# ADS.net
KiCad netlist of a schematic drawn in Altium Designer
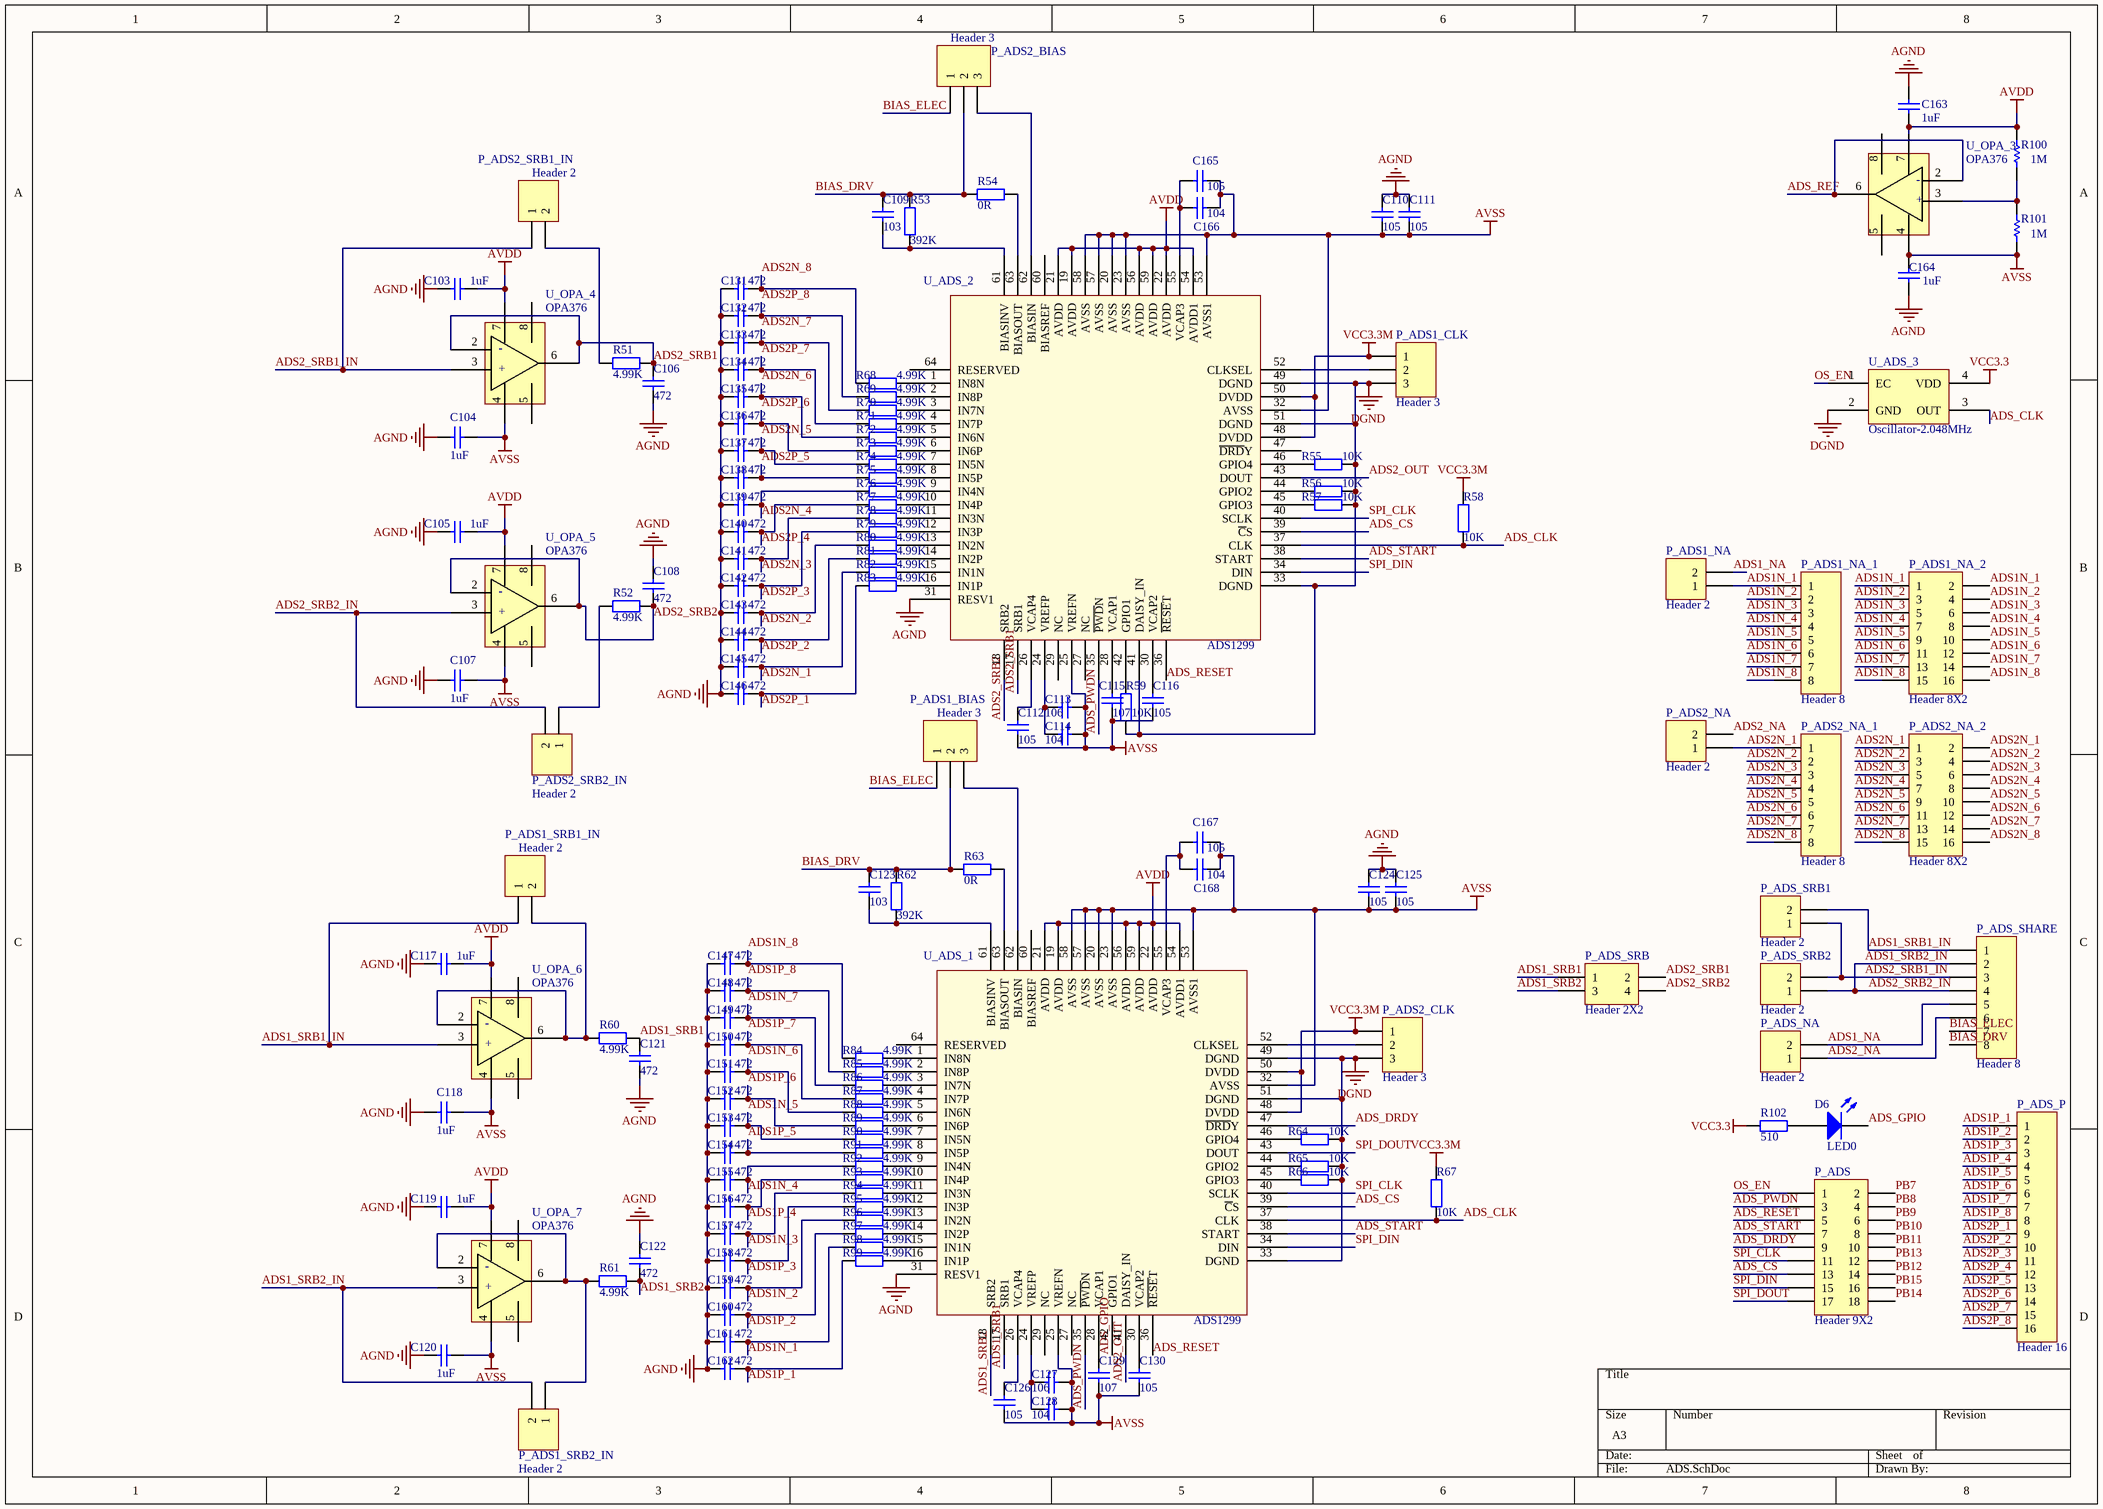
[diagram p0: ADS.SchDoc]

(export (version "E")
  (design (tool "Eeschema 10.0.6"))
  (components
    (comp (ref "C103")
      (value "1uF")
      (footprint "SMT-0603")
      (description "Capacitor")
      (fields (field (name "PUBLISHER") "Altium Limited"))
      (libsource (lib "Miscellaneous Devices") (part "Cap"))
    )
    (comp (ref "C104")
      (value "1uF")
      (footprint "SMT-0603")
      (description "Capacitor")
      (fields (field (name "PUBLISHER") "Altium Limited"))
      (libsource (lib "Miscellaneous Devices") (part "Cap"))
    )
    (comp (ref "C105")
      (value "1uF")
      (footprint "SMT-0603")
      (description "Capacitor")
      (fields (field (name "PUBLISHER") "Altium Limited"))
      (libsource (lib "Miscellaneous Devices") (part "Cap"))
    )
    (comp (ref "C106")
      (value "472")
      (footprint "SMT-0603")
      (description "Capacitor")
      (fields (field (name "Comment") "Cap") (field (name "PUBLISHER") "Altium Limited"))
      (libsource (lib "Miscellaneous Devices") (part "Cap"))
    )
    (comp (ref "C107")
      (value "1uF")
      (footprint "SMT-0603")
      (description "Capacitor")
      (fields (field (name "PUBLISHER") "Altium Limited"))
      (libsource (lib "Miscellaneous Devices") (part "Cap"))
    )
    (comp (ref "C108")
      (value "472")
      (footprint "SMT-0603")
      (description "Capacitor")
      (fields (field (name "Comment") "Cap") (field (name "PUBLISHER") "Altium Limited"))
      (libsource (lib "Miscellaneous Devices") (part "Cap"))
    )
    (comp (ref "C109")
      (value "103")
      (footprint "SMT-0603")
      (description "Capacitor")
      (fields (field (name "Comment") "Cap") (field (name "PUBLISHER") "Altium Limited"))
      (libsource (lib "Miscellaneous Devices") (part "Cap"))
    )
    (comp (ref "C110")
      (value "105")
      (footprint "SMT-0603")
      (description "Capacitor")
      (fields (field (name "Comment") "Cap") (field (name "PUBLISHER") "Altium Limited"))
      (libsource (lib "Miscellaneous Devices") (part "Cap"))
    )
    (comp (ref "C111")
      (value "105")
      (footprint "SMT-0603")
      (description "Capacitor")
      (fields (field (name "Comment") "Cap") (field (name "PUBLISHER") "Altium Limited"))
      (libsource (lib "Miscellaneous Devices") (part "Cap"))
    )
    (comp (ref "C112")
      (value "105")
      (footprint "SMT-0603")
      (description "Capacitor")
      (fields (field (name "Comment") "Cap") (field (name "PUBLISHER") "Altium Limited"))
      (libsource (lib "Miscellaneous Devices") (part "Cap"))
    )
    (comp (ref "C113")
      (value "106")
      (footprint "SMT-0603")
      (description "Capacitor")
      (fields (field (name "Comment") "Cap") (field (name "PUBLISHER") "Altium Limited"))
      (libsource (lib "Miscellaneous Devices") (part "Cap"))
    )
    (comp (ref "C114")
      (value "104")
      (footprint "SMT-0603")
      (description "Capacitor")
      (fields (field (name "Comment") "Cap") (field (name "PUBLISHER") "Altium Limited"))
      (libsource (lib "Miscellaneous Devices") (part "Cap"))
    )
    (comp (ref "C115")
      (value "107")
      (footprint "SMT-0603")
      (description "Capacitor")
      (fields (field (name "Comment") "Cap") (field (name "PUBLISHER") "Altium Limited"))
      (libsource (lib "Miscellaneous Devices") (part "Cap"))
    )
    (comp (ref "C116")
      (value "105")
      (footprint "SMT-0603")
      (description "Capacitor")
      (fields (field (name "Comment") "Cap") (field (name "PUBLISHER") "Altium Limited"))
      (libsource (lib "Miscellaneous Devices") (part "Cap"))
    )
    (comp (ref "C117")
      (value "1uF")
      (footprint "SMT-0603")
      (description "Capacitor")
      (fields (field (name "PUBLISHER") "Altium Limited"))
      (libsource (lib "Miscellaneous Devices") (part "Cap"))
    )
    (comp (ref "C118")
      (value "1uF")
      (footprint "SMT-0603")
      (description "Capacitor")
      (fields (field (name "PUBLISHER") "Altium Limited"))
      (libsource (lib "Miscellaneous Devices") (part "Cap"))
    )
    (comp (ref "C119")
      (value "1uF")
      (footprint "SMT-0603")
      (description "Capacitor")
      (fields (field (name "PUBLISHER") "Altium Limited"))
      (libsource (lib "Miscellaneous Devices") (part "Cap"))
    )
    (comp (ref "C120")
      (value "1uF")
      (footprint "SMT-0603")
      (description "Capacitor")
      (fields (field (name "PUBLISHER") "Altium Limited"))
      (libsource (lib "Miscellaneous Devices") (part "Cap"))
    )
    (comp (ref "C121")
      (value "472")
      (footprint "SMT-0603")
      (description "Capacitor")
      (fields (field (name "Comment") "Cap") (field (name "PUBLISHER") "Altium Limited"))
      (libsource (lib "Miscellaneous Devices") (part "Cap"))
    )
    (comp (ref "C122")
      (value "472")
      (footprint "SMT-0603")
      (description "Capacitor")
      (fields (field (name "Comment") "Cap") (field (name "PUBLISHER") "Altium Limited"))
      (libsource (lib "Miscellaneous Devices") (part "Cap"))
    )
    (comp (ref "C123")
      (value "103")
      (footprint "SMT-0603")
      (description "Capacitor")
      (fields (field (name "Comment") "Cap") (field (name "PUBLISHER") "Altium Limited"))
      (libsource (lib "Miscellaneous Devices") (part "Cap"))
    )
    (comp (ref "C124")
      (value "105")
      (footprint "SMT-0603")
      (description "Capacitor")
      (fields (field (name "Comment") "Cap") (field (name "PUBLISHER") "Altium Limited"))
      (libsource (lib "Miscellaneous Devices") (part "Cap"))
    )
    (comp (ref "C125")
      (value "105")
      (footprint "SMT-0603")
      (description "Capacitor")
      (fields (field (name "Comment") "Cap") (field (name "PUBLISHER") "Altium Limited"))
      (libsource (lib "Miscellaneous Devices") (part "Cap"))
    )
    (comp (ref "C126")
      (value "105")
      (footprint "SMT-0603")
      (description "Capacitor")
      (fields (field (name "Comment") "Cap") (field (name "PUBLISHER") "Altium Limited"))
      (libsource (lib "Miscellaneous Devices") (part "Cap"))
    )
    (comp (ref "C127")
      (value "106")
      (footprint "SMT-0603")
      (description "Capacitor")
      (fields (field (name "Comment") "Cap") (field (name "PUBLISHER") "Altium Limited"))
      (libsource (lib "Miscellaneous Devices") (part "Cap"))
    )
    (comp (ref "C128")
      (value "104")
      (footprint "SMT-0603")
      (description "Capacitor")
      (fields (field (name "Comment") "Cap") (field (name "PUBLISHER") "Altium Limited"))
      (libsource (lib "Miscellaneous Devices") (part "Cap"))
    )
    (comp (ref "C129")
      (value "107")
      (footprint "SMT-0603")
      (description "Capacitor")
      (fields (field (name "Comment") "Cap") (field (name "PUBLISHER") "Altium Limited"))
      (libsource (lib "Miscellaneous Devices") (part "Cap"))
    )
    (comp (ref "C130")
      (value "105")
      (footprint "SMT-0603")
      (description "Capacitor")
      (fields (field (name "Comment") "Cap") (field (name "PUBLISHER") "Altium Limited"))
      (libsource (lib "Miscellaneous Devices") (part "Cap"))
    )
    (comp (ref "C131")
      (value "472")
      (footprint "SMT-0603")
      (description "Capacitor")
      (fields (field (name "Comment") "Cap") (field (name "PUBLISHER") "Altium Limited"))
      (libsource (lib "Miscellaneous Devices") (part "Cap"))
    )
    (comp (ref "C132")
      (value "472")
      (footprint "SMT-0603")
      (description "Capacitor")
      (fields (field (name "Comment") "Cap") (field (name "PUBLISHER") "Altium Limited"))
      (libsource (lib "Miscellaneous Devices") (part "Cap"))
    )
    (comp (ref "C133")
      (value "472")
      (footprint "SMT-0603")
      (description "Capacitor")
      (fields (field (name "Comment") "Cap") (field (name "PUBLISHER") "Altium Limited"))
      (libsource (lib "Miscellaneous Devices") (part "Cap"))
    )
    (comp (ref "C134")
      (value "472")
      (footprint "SMT-0603")
      (description "Capacitor")
      (fields (field (name "Comment") "Cap") (field (name "PUBLISHER") "Altium Limited"))
      (libsource (lib "Miscellaneous Devices") (part "Cap"))
    )
    (comp (ref "C135")
      (value "472")
      (footprint "SMT-0603")
      (description "Capacitor")
      (fields (field (name "Comment") "Cap") (field (name "PUBLISHER") "Altium Limited"))
      (libsource (lib "Miscellaneous Devices") (part "Cap"))
    )
    (comp (ref "C136")
      (value "472")
      (footprint "SMT-0603")
      (description "Capacitor")
      (fields (field (name "Comment") "Cap") (field (name "PUBLISHER") "Altium Limited"))
      (libsource (lib "Miscellaneous Devices") (part "Cap"))
    )
    (comp (ref "C137")
      (value "472")
      (footprint "SMT-0603")
      (description "Capacitor")
      (fields (field (name "Comment") "Cap") (field (name "PUBLISHER") "Altium Limited"))
      (libsource (lib "Miscellaneous Devices") (part "Cap"))
    )
    (comp (ref "C138")
      (value "472")
      (footprint "SMT-0603")
      (description "Capacitor")
      (fields (field (name "Comment") "Cap") (field (name "PUBLISHER") "Altium Limited"))
      (libsource (lib "Miscellaneous Devices") (part "Cap"))
    )
    (comp (ref "C139")
      (value "472")
      (footprint "SMT-0603")
      (description "Capacitor")
      (fields (field (name "Comment") "Cap") (field (name "PUBLISHER") "Altium Limited"))
      (libsource (lib "Miscellaneous Devices") (part "Cap"))
    )
    (comp (ref "C140")
      (value "472")
      (footprint "SMT-0603")
      (description "Capacitor")
      (fields (field (name "Comment") "Cap") (field (name "PUBLISHER") "Altium Limited"))
      (libsource (lib "Miscellaneous Devices") (part "Cap"))
    )
    (comp (ref "C141")
      (value "472")
      (footprint "SMT-0603")
      (description "Capacitor")
      (fields (field (name "Comment") "Cap") (field (name "PUBLISHER") "Altium Limited"))
      (libsource (lib "Miscellaneous Devices") (part "Cap"))
    )
    (comp (ref "C142")
      (value "472")
      (footprint "SMT-0603")
      (description "Capacitor")
      (fields (field (name "Comment") "Cap") (field (name "PUBLISHER") "Altium Limited"))
      (libsource (lib "Miscellaneous Devices") (part "Cap"))
    )
    (comp (ref "C143")
      (value "472")
      (footprint "SMT-0603")
      (description "Capacitor")
      (fields (field (name "Comment") "Cap") (field (name "PUBLISHER") "Altium Limited"))
      (libsource (lib "Miscellaneous Devices") (part "Cap"))
    )
    (comp (ref "C144")
      (value "472")
      (footprint "SMT-0603")
      (description "Capacitor")
      (fields (field (name "Comment") "Cap") (field (name "PUBLISHER") "Altium Limited"))
      (libsource (lib "Miscellaneous Devices") (part "Cap"))
    )
    (comp (ref "C145")
      (value "472")
      (footprint "SMT-0603")
      (description "Capacitor")
      (fields (field (name "Comment") "Cap") (field (name "PUBLISHER") "Altium Limited"))
      (libsource (lib "Miscellaneous Devices") (part "Cap"))
    )
    (comp (ref "C146")
      (value "472")
      (footprint "SMT-0603")
      (description "Capacitor")
      (fields (field (name "Comment") "Cap") (field (name "PUBLISHER") "Altium Limited"))
      (libsource (lib "Miscellaneous Devices") (part "Cap"))
    )
    (comp (ref "C147")
      (value "472")
      (footprint "SMT-0603")
      (description "Capacitor")
      (fields (field (name "Comment") "Cap") (field (name "PUBLISHER") "Altium Limited"))
      (libsource (lib "Miscellaneous Devices") (part "Cap"))
    )
    (comp (ref "C148")
      (value "472")
      (footprint "SMT-0603")
      (description "Capacitor")
      (fields (field (name "Comment") "Cap") (field (name "PUBLISHER") "Altium Limited"))
      (libsource (lib "Miscellaneous Devices") (part "Cap"))
    )
    (comp (ref "C149")
      (value "472")
      (footprint "SMT-0603")
      (description "Capacitor")
      (fields (field (name "Comment") "Cap") (field (name "PUBLISHER") "Altium Limited"))
      (libsource (lib "Miscellaneous Devices") (part "Cap"))
    )
    (comp (ref "C150")
      (value "472")
      (footprint "SMT-0603")
      (description "Capacitor")
      (fields (field (name "Comment") "Cap") (field (name "PUBLISHER") "Altium Limited"))
      (libsource (lib "Miscellaneous Devices") (part "Cap"))
    )
    (comp (ref "C151")
      (value "472")
      (footprint "SMT-0603")
      (description "Capacitor")
      (fields (field (name "Comment") "Cap") (field (name "PUBLISHER") "Altium Limited"))
      (libsource (lib "Miscellaneous Devices") (part "Cap"))
    )
    (comp (ref "C152")
      (value "472")
      (footprint "SMT-0603")
      (description "Capacitor")
      (fields (field (name "Comment") "Cap") (field (name "PUBLISHER") "Altium Limited"))
      (libsource (lib "Miscellaneous Devices") (part "Cap"))
    )
    (comp (ref "C153")
      (value "472")
      (footprint "SMT-0603")
      (description "Capacitor")
      (fields (field (name "Comment") "Cap") (field (name "PUBLISHER") "Altium Limited"))
      (libsource (lib "Miscellaneous Devices") (part "Cap"))
    )
    (comp (ref "C154")
      (value "472")
      (footprint "SMT-0603")
      (description "Capacitor")
      (fields (field (name "Comment") "Cap") (field (name "PUBLISHER") "Altium Limited"))
      (libsource (lib "Miscellaneous Devices") (part "Cap"))
    )
    (comp (ref "C155")
      (value "472")
      (footprint "SMT-0603")
      (description "Capacitor")
      (fields (field (name "Comment") "Cap") (field (name "PUBLISHER") "Altium Limited"))
      (libsource (lib "Miscellaneous Devices") (part "Cap"))
    )
    (comp (ref "C156")
      (value "472")
      (footprint "SMT-0603")
      (description "Capacitor")
      (fields (field (name "Comment") "Cap") (field (name "PUBLISHER") "Altium Limited"))
      (libsource (lib "Miscellaneous Devices") (part "Cap"))
    )
    (comp (ref "C157")
      (value "472")
      (footprint "SMT-0603")
      (description "Capacitor")
      (fields (field (name "Comment") "Cap") (field (name "PUBLISHER") "Altium Limited"))
      (libsource (lib "Miscellaneous Devices") (part "Cap"))
    )
    (comp (ref "C158")
      (value "472")
      (footprint "SMT-0603")
      (description "Capacitor")
      (fields (field (name "Comment") "Cap") (field (name "PUBLISHER") "Altium Limited"))
      (libsource (lib "Miscellaneous Devices") (part "Cap"))
    )
    (comp (ref "C159")
      (value "472")
      (footprint "SMT-0603")
      (description "Capacitor")
      (fields (field (name "Comment") "Cap") (field (name "PUBLISHER") "Altium Limited"))
      (libsource (lib "Miscellaneous Devices") (part "Cap"))
    )
    (comp (ref "C160")
      (value "472")
      (footprint "SMT-0603")
      (description "Capacitor")
      (fields (field (name "Comment") "Cap") (field (name "PUBLISHER") "Altium Limited"))
      (libsource (lib "Miscellaneous Devices") (part "Cap"))
    )
    (comp (ref "C161")
      (value "472")
      (footprint "SMT-0603")
      (description "Capacitor")
      (fields (field (name "Comment") "Cap") (field (name "PUBLISHER") "Altium Limited"))
      (libsource (lib "Miscellaneous Devices") (part "Cap"))
    )
    (comp (ref "C162")
      (value "472")
      (footprint "SMT-0603")
      (description "Capacitor")
      (fields (field (name "Comment") "Cap") (field (name "PUBLISHER") "Altium Limited"))
      (libsource (lib "Miscellaneous Devices") (part "Cap"))
    )
    (comp (ref "C163")
      (value "1uF")
      (footprint "SMT-0603")
      (description "Capacitor")
      (fields (field (name "PUBLISHER") "Altium Limited"))
      (libsource (lib "Miscellaneous Devices") (part "Cap"))
    )
    (comp (ref "C164")
      (value "1uF")
      (footprint "SMT-0603")
      (description "Capacitor")
      (fields (field (name "PUBLISHER") "Altium Limited"))
      (libsource (lib "Miscellaneous Devices") (part "Cap"))
    )
    (comp (ref "C165")
      (value "105")
      (footprint "SMT-0603")
      (description "Capacitor")
      (fields (field (name "Comment") "Cap") (field (name "PUBLISHER") "Altium Limited"))
      (libsource (lib "Miscellaneous Devices") (part "Cap"))
    )
    (comp (ref "C166")
      (value "104")
      (footprint "SMT-0603")
      (description "Capacitor")
      (fields (field (name "Comment") "Cap") (field (name "PUBLISHER") "Altium Limited"))
      (libsource (lib "Miscellaneous Devices") (part "Cap"))
    )
    (comp (ref "C167")
      (value "105")
      (footprint "SMT-0603")
      (description "Capacitor")
      (fields (field (name "Comment") "Cap") (field (name "PUBLISHER") "Altium Limited"))
      (libsource (lib "Miscellaneous Devices") (part "Cap"))
    )
    (comp (ref "C168")
      (value "104")
      (footprint "SMT-0603")
      (description "Capacitor")
      (fields (field (name "Comment") "Cap") (field (name "PUBLISHER") "Altium Limited"))
      (libsource (lib "Miscellaneous Devices") (part "Cap"))
    )
    (comp (ref "D6")
      (value "LED0")
      (footprint "K3528")
      (description "Typical INFRARED GaAs LED")
      (fields (field (name "PUBLISHER") "Altium Limited"))
      (libsource (lib "Miscellaneous Devices") (part "LED0"))
    )
    (comp (ref "P_ADS")
      (value "Header 9X2")
      (footprint "HDR2X9")
      (description "Header, 9-Pin, Dual row")
      (fields (field (name "PUBLISHER") "Altium Limited"))
      (libsource (lib "Miscellaneous Connectors") (part "Header 9X2"))
    )
    (comp (ref "P_ADS1_BIAS")
      (value "Header 3")
      (footprint "HDR1X3")
      (description "Header, 3-Pin")
      (fields (field (name "PUBLISHER") "Altium Limited"))
      (libsource (lib "Miscellaneous Connectors") (part "Header 3"))
    )
    (comp (ref "P_ADS1_CLK")
      (value "Header 3")
      (footprint "HDR1X3")
      (description "Header, 3-Pin")
      (fields (field (name "PUBLISHER") "Altium Limited"))
      (libsource (lib "") (part "Header 3_1"))
    )
    (comp (ref "P_ADS1_NA")
      (value "Header 2")
      (footprint "HDR1X2")
      (description "Header, 2-Pin")
      (fields (field (name "PUBLISHER") "Altium Limited"))
      (libsource (lib "Miscellaneous Connectors") (part "Header 2"))
    )
    (comp (ref "P_ADS1_NA_1")
      (value "Header 8")
      (footprint "HDR1X8")
      (description "Header, 8-Pin")
      (fields (field (name "PUBLISHER") "Altium Limited"))
      (libsource (lib "Miscellaneous Connectors") (part "Header 8"))
    )
    (comp (ref "P_ADS1_NA_2")
      (value "Header 8X2")
      (footprint "HDR2X8")
      (description "Header, 8-Pin, Dual row")
      (fields (field (name "PUBLISHER") "Altium Limited"))
      (libsource (lib "Miscellaneous Connectors") (part "Header 8X2"))
    )
    (comp (ref "P_ADS1_SRB1_IN")
      (value "Header 2")
      (footprint "HDR1X2")
      (description "Header, 2-Pin")
      (fields (field (name "PUBLISHER") "Altium Limited"))
      (libsource (lib "") (part "Header 2_1"))
    )
    (comp (ref "P_ADS1_SRB2_IN")
      (value "Header 2")
      (footprint "HDR1X2")
      (description "Header, 2-Pin")
      (fields (field (name "PUBLISHER") "Altium Limited"))
      (libsource (lib "") (part "Header 2_2"))
    )
    (comp (ref "P_ADS2_BIAS")
      (value "Header 3")
      (footprint "HDR1X3")
      (description "Header, 3-Pin")
      (fields (field (name "PUBLISHER") "Altium Limited"))
      (libsource (lib "Miscellaneous Connectors") (part "Header 3"))
    )
    (comp (ref "P_ADS2_CLK")
      (value "Header 3")
      (footprint "HDR1X3")
      (description "Header, 3-Pin")
      (fields (field (name "PUBLISHER") "Altium Limited"))
      (libsource (lib "") (part "Header 3_1"))
    )
    (comp (ref "P_ADS2_NA")
      (value "Header 2")
      (footprint "HDR1X2")
      (description "Header, 2-Pin")
      (fields (field (name "PUBLISHER") "Altium Limited"))
      (libsource (lib "Miscellaneous Connectors") (part "Header 2"))
    )
    (comp (ref "P_ADS2_NA_1")
      (value "Header 8")
      (footprint "HDR1X8")
      (description "Header, 8-Pin")
      (fields (field (name "PUBLISHER") "Altium Limited"))
      (libsource (lib "Miscellaneous Connectors") (part "Header 8"))
    )
    (comp (ref "P_ADS2_NA_2")
      (value "Header 8X2")
      (footprint "HDR2X8")
      (description "Header, 8-Pin, Dual row")
      (fields (field (name "PUBLISHER") "Altium Limited"))
      (libsource (lib "Miscellaneous Connectors") (part "Header 8X2"))
    )
    (comp (ref "P_ADS2_SRB1_IN")
      (value "Header 2")
      (footprint "HDR1X2")
      (description "Header, 2-Pin")
      (fields (field (name "PUBLISHER") "Altium Limited"))
      (libsource (lib "") (part "Header 2_1"))
    )
    (comp (ref "P_ADS2_SRB2_IN")
      (value "Header 2")
      (footprint "HDR1X2")
      (description "Header, 2-Pin")
      (fields (field (name "PUBLISHER") "Altium Limited"))
      (libsource (lib "") (part "Header 2_2"))
    )
    (comp (ref "P_ADS_NA")
      (value "Header 2")
      (footprint "HDR1X2")
      (description "Header, 2-Pin")
      (fields (field (name "PUBLISHER") "Altium Limited"))
      (libsource (lib "Miscellaneous Connectors") (part "Header 2"))
    )
    (comp (ref "P_ADS_P")
      (value "Header 16")
      (footprint "HDR1X16")
      (description "Header, 16-Pin")
      (fields (field (name "PUBLISHER") "Altium Limited"))
      (libsource (lib "Miscellaneous Connectors") (part "Header 16"))
    )
    (comp (ref "P_ADS_SHARE")
      (value "Header 8")
      (footprint "HDR1X8")
      (description "Header, 8-Pin")
      (fields (field (name "PUBLISHER") "Altium Limited"))
      (libsource (lib "Miscellaneous Connectors") (part "Header 8"))
    )
    (comp (ref "P_ADS_SRB")
      (value "Header 2X2")
      (footprint "HDR2X2")
      (description "Header, 2-Pin, Dual row")
      (fields (field (name "PUBLISHER") "Altium Limited"))
      (libsource (lib "Miscellaneous Connectors") (part "Header 2X2"))
    )
    (comp (ref "P_ADS_SRB1")
      (value "Header 2")
      (footprint "HDR1X2")
      (description "Header, 2-Pin")
      (fields (field (name "PUBLISHER") "Altium Limited"))
      (libsource (lib "Miscellaneous Connectors") (part "Header 2"))
    )
    (comp (ref "P_ADS_SRB2")
      (value "Header 2")
      (footprint "HDR1X2")
      (description "Header, 2-Pin")
      (fields (field (name "PUBLISHER") "Altium Limited"))
      (libsource (lib "Miscellaneous Connectors") (part "Header 2"))
    )
    (comp (ref "R51")
      (value "4.99K")
      (footprint "SMT-0603")
      (description "Resistor")
      (fields (field (name "Comment") "Res2") (field (name "PUBLISHER") "Altium Limited"))
      (libsource (lib "Miscellaneous Devices") (part "Res2"))
    )
    (comp (ref "R52")
      (value "4.99K")
      (footprint "SMT-0603")
      (description "Resistor")
      (fields (field (name "Comment") "Res2") (field (name "PUBLISHER") "Altium Limited"))
      (libsource (lib "Miscellaneous Devices") (part "Res2"))
    )
    (comp (ref "R53")
      (value "392K")
      (footprint "SMT-0603")
      (description "Resistor")
      (fields (field (name "Comment") "Res2") (field (name "PUBLISHER") "Altium Limited"))
      (libsource (lib "") (part "Res2_1"))
    )
    (comp (ref "R54")
      (value "0R")
      (footprint "SMT-0603")
      (description "Resistor")
      (fields (field (name "Comment") "Res2") (field (name "PUBLISHER") "Altium Limited"))
      (libsource (lib "Miscellaneous Devices") (part "Res2"))
    )
    (comp (ref "R55")
      (value "10K")
      (footprint "SMT-0603")
      (description "Resistor")
      (fields (field (name "Comment") "Res2") (field (name "PUBLISHER") "Altium Limited"))
      (libsource (lib "Miscellaneous Devices") (part "Res2"))
    )
    (comp (ref "R56")
      (value "10K")
      (footprint "SMT-0603")
      (description "Resistor")
      (fields (field (name "Comment") "Res2") (field (name "PUBLISHER") "Altium Limited"))
      (libsource (lib "Miscellaneous Devices") (part "Res2"))
    )
    (comp (ref "R57")
      (value "10K")
      (footprint "SMT-0603")
      (description "Resistor")
      (fields (field (name "Comment") "Res2") (field (name "PUBLISHER") "Altium Limited"))
      (libsource (lib "Miscellaneous Devices") (part "Res2"))
    )
    (comp (ref "R58")
      (value "10K")
      (footprint "SMT-0603")
      (description "Resistor")
      (fields (field (name "Comment") "Res2") (field (name "PUBLISHER") "Altium Limited"))
      (libsource (lib "") (part "Res2_1"))
    )
    (comp (ref "R59")
      (value "10K")
      (footprint "SMT-0603")
      (description "Resistor")
      (fields (field (name "Comment") "Res2") (field (name "PUBLISHER") "Altium Limited"))
      (libsource (lib "") (part "Res2_1"))
    )
    (comp (ref "R60")
      (value "4.99K")
      (footprint "SMT-0603")
      (description "Resistor")
      (fields (field (name "Comment") "Res2") (field (name "PUBLISHER") "Altium Limited"))
      (libsource (lib "Miscellaneous Devices") (part "Res2"))
    )
    (comp (ref "R61")
      (value "4.99K")
      (footprint "SMT-0603")
      (description "Resistor")
      (fields (field (name "Comment") "Res2") (field (name "PUBLISHER") "Altium Limited"))
      (libsource (lib "Miscellaneous Devices") (part "Res2"))
    )
    (comp (ref "R62")
      (value "392K")
      (footprint "SMT-0603")
      (description "Resistor")
      (fields (field (name "Comment") "Res2") (field (name "PUBLISHER") "Altium Limited"))
      (libsource (lib "") (part "Res2_1"))
    )
    (comp (ref "R63")
      (value "0R")
      (footprint "SMT-0603")
      (description "Resistor")
      (fields (field (name "Comment") "Res2") (field (name "PUBLISHER") "Altium Limited"))
      (libsource (lib "Miscellaneous Devices") (part "Res2"))
    )
    (comp (ref "R64")
      (value "10K")
      (footprint "SMT-0603")
      (description "Resistor")
      (fields (field (name "Comment") "Res2") (field (name "PUBLISHER") "Altium Limited"))
      (libsource (lib "Miscellaneous Devices") (part "Res2"))
    )
    (comp (ref "R65")
      (value "10K")
      (footprint "SMT-0603")
      (description "Resistor")
      (fields (field (name "Comment") "Res2") (field (name "PUBLISHER") "Altium Limited"))
      (libsource (lib "Miscellaneous Devices") (part "Res2"))
    )
    (comp (ref "R66")
      (value "10K")
      (footprint "SMT-0603")
      (description "Resistor")
      (fields (field (name "Comment") "Res2") (field (name "PUBLISHER") "Altium Limited"))
      (libsource (lib "Miscellaneous Devices") (part "Res2"))
    )
    (comp (ref "R67")
      (value "10K")
      (footprint "SMT-0603")
      (description "Resistor")
      (fields (field (name "Comment") "Res2") (field (name "PUBLISHER") "Altium Limited"))
      (libsource (lib "") (part "Res2_1"))
    )
    (comp (ref "R68")
      (value "4.99K")
      (footprint "SMT-0603")
      (description "Resistor")
      (fields (field (name "Comment") "Res2") (field (name "PUBLISHER") "Altium Limited"))
      (libsource (lib "Miscellaneous Devices") (part "Res2"))
    )
    (comp (ref "R69")
      (value "4.99K")
      (footprint "SMT-0603")
      (description "Resistor")
      (fields (field (name "Comment") "Res2") (field (name "PUBLISHER") "Altium Limited"))
      (libsource (lib "Miscellaneous Devices") (part "Res2"))
    )
    (comp (ref "R70")
      (value "4.99K")
      (footprint "SMT-0603")
      (description "Resistor")
      (fields (field (name "Comment") "Res2") (field (name "PUBLISHER") "Altium Limited"))
      (libsource (lib "Miscellaneous Devices") (part "Res2"))
    )
    (comp (ref "R71")
      (value "4.99K")
      (footprint "SMT-0603")
      (description "Resistor")
      (fields (field (name "Comment") "Res2") (field (name "PUBLISHER") "Altium Limited"))
      (libsource (lib "Miscellaneous Devices") (part "Res2"))
    )
    (comp (ref "R72")
      (value "4.99K")
      (footprint "SMT-0603")
      (description "Resistor")
      (fields (field (name "Comment") "Res2") (field (name "PUBLISHER") "Altium Limited"))
      (libsource (lib "Miscellaneous Devices") (part "Res2"))
    )
    (comp (ref "R73")
      (value "4.99K")
      (footprint "SMT-0603")
      (description "Resistor")
      (fields (field (name "Comment") "Res2") (field (name "PUBLISHER") "Altium Limited"))
      (libsource (lib "Miscellaneous Devices") (part "Res2"))
    )
    (comp (ref "R74")
      (value "4.99K")
      (footprint "SMT-0603")
      (description "Resistor")
      (fields (field (name "Comment") "Res2") (field (name "PUBLISHER") "Altium Limited"))
      (libsource (lib "Miscellaneous Devices") (part "Res2"))
    )
    (comp (ref "R75")
      (value "4.99K")
      (footprint "SMT-0603")
      (description "Resistor")
      (fields (field (name "Comment") "Res2") (field (name "PUBLISHER") "Altium Limited"))
      (libsource (lib "Miscellaneous Devices") (part "Res2"))
    )
    (comp (ref "R76")
      (value "4.99K")
      (footprint "SMT-0603")
      (description "Resistor")
      (fields (field (name "Comment") "Res2") (field (name "PUBLISHER") "Altium Limited"))
      (libsource (lib "Miscellaneous Devices") (part "Res2"))
    )
    (comp (ref "R77")
      (value "4.99K")
      (footprint "SMT-0603")
      (description "Resistor")
      (fields (field (name "Comment") "Res2") (field (name "PUBLISHER") "Altium Limited"))
      (libsource (lib "Miscellaneous Devices") (part "Res2"))
    )
    (comp (ref "R78")
      (value "4.99K")
      (footprint "SMT-0603")
      (description "Resistor")
      (fields (field (name "Comment") "Res2") (field (name "PUBLISHER") "Altium Limited"))
      (libsource (lib "Miscellaneous Devices") (part "Res2"))
    )
    (comp (ref "R79")
      (value "4.99K")
      (footprint "SMT-0603")
      (description "Resistor")
      (fields (field (name "Comment") "Res2") (field (name "PUBLISHER") "Altium Limited"))
      (libsource (lib "Miscellaneous Devices") (part "Res2"))
    )
    (comp (ref "R80")
      (value "4.99K")
      (footprint "SMT-0603")
      (description "Resistor")
      (fields (field (name "Comment") "Res2") (field (name "PUBLISHER") "Altium Limited"))
      (libsource (lib "Miscellaneous Devices") (part "Res2"))
    )
    (comp (ref "R81")
      (value "4.99K")
      (footprint "SMT-0603")
      (description "Resistor")
      (fields (field (name "Comment") "Res2") (field (name "PUBLISHER") "Altium Limited"))
      (libsource (lib "Miscellaneous Devices") (part "Res2"))
    )
    (comp (ref "R82")
      (value "4.99K")
      (footprint "SMT-0603")
      (description "Resistor")
      (fields (field (name "Comment") "Res2") (field (name "PUBLISHER") "Altium Limited"))
      (libsource (lib "Miscellaneous Devices") (part "Res2"))
    )
    (comp (ref "R83")
      (value "4.99K")
      (footprint "SMT-0603")
      (description "Resistor")
      (fields (field (name "Comment") "Res2") (field (name "PUBLISHER") "Altium Limited"))
      (libsource (lib "Miscellaneous Devices") (part "Res2"))
    )
    (comp (ref "R84")
      (value "4.99K")
      (footprint "SMT-0603")
      (description "Resistor")
      (fields (field (name "Comment") "Res2") (field (name "PUBLISHER") "Altium Limited"))
      (libsource (lib "Miscellaneous Devices") (part "Res2"))
    )
    (comp (ref "R85")
      (value "4.99K")
      (footprint "SMT-0603")
      (description "Resistor")
      (fields (field (name "Comment") "Res2") (field (name "PUBLISHER") "Altium Limited"))
      (libsource (lib "Miscellaneous Devices") (part "Res2"))
    )
    (comp (ref "R86")
      (value "4.99K")
      (footprint "SMT-0603")
      (description "Resistor")
      (fields (field (name "Comment") "Res2") (field (name "PUBLISHER") "Altium Limited"))
      (libsource (lib "Miscellaneous Devices") (part "Res2"))
    )
    (comp (ref "R87")
      (value "4.99K")
      (footprint "SMT-0603")
      (description "Resistor")
      (fields (field (name "Comment") "Res2") (field (name "PUBLISHER") "Altium Limited"))
      (libsource (lib "Miscellaneous Devices") (part "Res2"))
    )
    (comp (ref "R88")
      (value "4.99K")
      (footprint "SMT-0603")
      (description "Resistor")
      (fields (field (name "Comment") "Res2") (field (name "PUBLISHER") "Altium Limited"))
      (libsource (lib "Miscellaneous Devices") (part "Res2"))
    )
    (comp (ref "R89")
      (value "4.99K")
      (footprint "SMT-0603")
      (description "Resistor")
      (fields (field (name "Comment") "Res2") (field (name "PUBLISHER") "Altium Limited"))
      (libsource (lib "Miscellaneous Devices") (part "Res2"))
    )
    (comp (ref "R90")
      (value "4.99K")
      (footprint "SMT-0603")
      (description "Resistor")
      (fields (field (name "Comment") "Res2") (field (name "PUBLISHER") "Altium Limited"))
      (libsource (lib "Miscellaneous Devices") (part "Res2"))
    )
    (comp (ref "R91")
      (value "4.99K")
      (footprint "SMT-0603")
      (description "Resistor")
      (fields (field (name "Comment") "Res2") (field (name "PUBLISHER") "Altium Limited"))
      (libsource (lib "Miscellaneous Devices") (part "Res2"))
    )
    (comp (ref "R92")
      (value "4.99K")
      (footprint "SMT-0603")
      (description "Resistor")
      (fields (field (name "Comment") "Res2") (field (name "PUBLISHER") "Altium Limited"))
      (libsource (lib "Miscellaneous Devices") (part "Res2"))
    )
    (comp (ref "R93")
      (value "4.99K")
      (footprint "SMT-0603")
      (description "Resistor")
      (fields (field (name "Comment") "Res2") (field (name "PUBLISHER") "Altium Limited"))
      (libsource (lib "Miscellaneous Devices") (part "Res2"))
    )
    (comp (ref "R94")
      (value "4.99K")
      (footprint "SMT-0603")
      (description "Resistor")
      (fields (field (name "Comment") "Res2") (field (name "PUBLISHER") "Altium Limited"))
      (libsource (lib "Miscellaneous Devices") (part "Res2"))
    )
    (comp (ref "R95")
      (value "4.99K")
      (footprint "SMT-0603")
      (description "Resistor")
      (fields (field (name "Comment") "Res2") (field (name "PUBLISHER") "Altium Limited"))
      (libsource (lib "Miscellaneous Devices") (part "Res2"))
    )
    (comp (ref "R96")
      (value "4.99K")
      (footprint "SMT-0603")
      (description "Resistor")
      (fields (field (name "Comment") "Res2") (field (name "PUBLISHER") "Altium Limited"))
      (libsource (lib "Miscellaneous Devices") (part "Res2"))
    )
    (comp (ref "R97")
      (value "4.99K")
      (footprint "SMT-0603")
      (description "Resistor")
      (fields (field (name "Comment") "Res2") (field (name "PUBLISHER") "Altium Limited"))
      (libsource (lib "Miscellaneous Devices") (part "Res2"))
    )
    (comp (ref "R98")
      (value "4.99K")
      (footprint "SMT-0603")
      (description "Resistor")
      (fields (field (name "Comment") "Res2") (field (name "PUBLISHER") "Altium Limited"))
      (libsource (lib "Miscellaneous Devices") (part "Res2"))
    )
    (comp (ref "R99")
      (value "4.99K")
      (footprint "SMT-0603")
      (description "Resistor")
      (fields (field (name "Comment") "Res2") (field (name "PUBLISHER") "Altium Limited"))
      (libsource (lib "Miscellaneous Devices") (part "Res2"))
    )
    (comp (ref "R100")
      (value "1M")
      (footprint "SMT-0603")
      (description "Resistor")
      (fields (field (name "PUBLISHER") "Altium Limited"))
      (libsource (lib "Miscellaneous Devices") (part "Res1"))
    )
    (comp (ref "R101")
      (value "1M")
      (footprint "SMT-0603")
      (description "Resistor")
      (fields (field (name "PUBLISHER") "Altium Limited"))
      (libsource (lib "Miscellaneous Devices") (part "Res1"))
    )
    (comp (ref "R102")
      (value "510")
      (footprint "SMT-0603")
      (description "Resistor")
      (fields (field (name "Comment") "Res2") (field (name "PUBLISHER") "Altium Limited"))
      (libsource (lib "Miscellaneous Devices") (part "Res2"))
    )
    (comp (ref "U_ADS_1") (value "ADS1299") (footprint "LQFP64") (libsource (lib "*") (part "ADS1299")))
    (comp (ref "U_ADS_2") (value "ADS1299") (footprint "LQFP64") (libsource (lib "*") (part "ADS1299")))
    (comp (ref "U_ADS_3")
      (value "Oscillator-2.048MHz")
      (footprint "3225")
      (libsource (lib "STM_ALL") (part "Oscillator-2.048MHz"))
    )
    (comp (ref "U_OPA_3") (value "OPA376") (footprint "SOP8") (libsource (lib "") (part "OPA376_1")))
    (comp (ref "U_OPA_4") (value "OPA376") (footprint "SOP8") (libsource (lib "*") (part "OPA376")))
    (comp (ref "U_OPA_5") (value "OPA376") (footprint "SOP8") (libsource (lib "*") (part "OPA376")))
    (comp (ref "U_OPA_6") (value "OPA376") (footprint "SOP8") (libsource (lib "*") (part "OPA376")))
    (comp (ref "U_OPA_7") (value "OPA376") (footprint "SOP8") (libsource (lib "*") (part "OPA376")))
  )
  (nets
    (net (code "1") (name "/ADS1N_1") (class "Default")
      (node (ref "C161") (pin "2") (pinfunction "2_2") (pintype "passive"))
      (node (ref "P_ADS1_NA") (pin "1") (pinfunction "1_1") (pintype "passive"))
      (node (ref "P_ADS1_NA_1") (pin "1") (pinfunction "1_1") (pintype "passive"))
      (node (ref "P_ADS1_NA_2") (pin "1") (pinfunction "1_1") (pintype "passive"))
      (node (ref "P_ADS1_NA_2") (pin "2") (pinfunction "2_2") (pintype "passive"))
      (node (ref "R98") (pin "1") (pinfunction "1_1") (pintype "passive"))
    )
    (net (code "2") (name "/ADS1N_2") (class "Default")
      (node (ref "C159") (pin "2") (pinfunction "2_2") (pintype "passive"))
      (node (ref "P_ADS1_NA_1") (pin "2") (pinfunction "2_2") (pintype "passive"))
      (node (ref "P_ADS1_NA_2") (pin "3") (pinfunction "3_3") (pintype "passive"))
      (node (ref "P_ADS1_NA_2") (pin "4") (pinfunction "4_4") (pintype "passive"))
      (node (ref "R96") (pin "1") (pinfunction "1_1") (pintype "passive"))
    )
    (net (code "3") (name "/ADS1N_3") (class "Default")
      (node (ref "C157") (pin "2") (pinfunction "2_2") (pintype "passive"))
      (node (ref "P_ADS1_NA_1") (pin "3") (pinfunction "3_3") (pintype "passive"))
      (node (ref "P_ADS1_NA_2") (pin "5") (pinfunction "5_5") (pintype "passive"))
      (node (ref "P_ADS1_NA_2") (pin "6") (pinfunction "6_6") (pintype "passive"))
      (node (ref "R94") (pin "1") (pinfunction "1_1") (pintype "passive"))
    )
    (net (code "4") (name "/ADS1N_4") (class "Default")
      (node (ref "C155") (pin "2") (pinfunction "2_2") (pintype "passive"))
      (node (ref "P_ADS1_NA_1") (pin "4") (pinfunction "4_4") (pintype "passive"))
      (node (ref "P_ADS1_NA_2") (pin "7") (pinfunction "7_7") (pintype "passive"))
      (node (ref "P_ADS1_NA_2") (pin "8") (pinfunction "8_8") (pintype "passive"))
      (node (ref "R92") (pin "1") (pinfunction "1_1") (pintype "passive"))
    )
    (net (code "5") (name "/ADS1N_5") (class "Default")
      (node (ref "C153") (pin "2") (pinfunction "2_2") (pintype "passive"))
      (node (ref "P_ADS1_NA_1") (pin "5") (pinfunction "5_5") (pintype "passive"))
      (node (ref "P_ADS1_NA_2") (pin "10") (pinfunction "10_10") (pintype "passive"))
      (node (ref "P_ADS1_NA_2") (pin "9") (pinfunction "9_9") (pintype "passive"))
      (node (ref "R90") (pin "1") (pinfunction "1_1") (pintype "passive"))
    )
    (net (code "6") (name "/ADS1N_6") (class "Default")
      (node (ref "C151") (pin "2") (pinfunction "2_2") (pintype "passive"))
      (node (ref "P_ADS1_NA_1") (pin "6") (pinfunction "6_6") (pintype "passive"))
      (node (ref "P_ADS1_NA_2") (pin "11") (pinfunction "11_11") (pintype "passive"))
      (node (ref "P_ADS1_NA_2") (pin "12") (pinfunction "12_12") (pintype "passive"))
      (node (ref "R88") (pin "1") (pinfunction "1_1") (pintype "passive"))
    )
    (net (code "7") (name "/ADS1N_7") (class "Default")
      (node (ref "C149") (pin "2") (pinfunction "2_2") (pintype "passive"))
      (node (ref "P_ADS1_NA_1") (pin "7") (pinfunction "7_7") (pintype "passive"))
      (node (ref "P_ADS1_NA_2") (pin "13") (pinfunction "13_13") (pintype "passive"))
      (node (ref "P_ADS1_NA_2") (pin "14") (pinfunction "14_14") (pintype "passive"))
      (node (ref "R86") (pin "1") (pinfunction "1_1") (pintype "passive"))
    )
    (net (code "8") (name "/ADS1N_8") (class "Default")
      (node (ref "C147") (pin "2") (pinfunction "2_2") (pintype "passive"))
      (node (ref "P_ADS1_NA_1") (pin "8") (pinfunction "8_8") (pintype "passive"))
      (node (ref "P_ADS1_NA_2") (pin "15") (pinfunction "15_15") (pintype "passive"))
      (node (ref "P_ADS1_NA_2") (pin "16") (pinfunction "16_16") (pintype "passive"))
      (node (ref "R84") (pin "1") (pinfunction "1_1") (pintype "passive"))
    )
    (net (code "9") (name "/ADS1P_1") (class "Default")
      (node (ref "C162") (pin "2") (pinfunction "2_2") (pintype "passive"))
      (node (ref "P_ADS_P") (pin "1") (pinfunction "1_1") (pintype "passive"))
      (node (ref "R99") (pin "1") (pinfunction "1_1") (pintype "passive"))
    )
    (net (code "10") (name "/ADS1P_2") (class "Default")
      (node (ref "C160") (pin "2") (pinfunction "2_2") (pintype "passive"))
      (node (ref "P_ADS_P") (pin "2") (pinfunction "2_2") (pintype "passive"))
      (node (ref "R97") (pin "1") (pinfunction "1_1") (pintype "passive"))
    )
    (net (code "11") (name "/ADS1P_3") (class "Default")
      (node (ref "C158") (pin "2") (pinfunction "2_2") (pintype "passive"))
      (node (ref "P_ADS_P") (pin "3") (pinfunction "3_3") (pintype "passive"))
      (node (ref "R95") (pin "1") (pinfunction "1_1") (pintype "passive"))
    )
    (net (code "12") (name "/ADS1P_4") (class "Default")
      (node (ref "C156") (pin "2") (pinfunction "2_2") (pintype "passive"))
      (node (ref "P_ADS_P") (pin "4") (pinfunction "4_4") (pintype "passive"))
      (node (ref "R93") (pin "1") (pinfunction "1_1") (pintype "passive"))
    )
    (net (code "13") (name "/ADS1P_5") (class "Default")
      (node (ref "C154") (pin "2") (pinfunction "2_2") (pintype "passive"))
      (node (ref "P_ADS_P") (pin "5") (pinfunction "5_5") (pintype "passive"))
      (node (ref "R91") (pin "1") (pinfunction "1_1") (pintype "passive"))
    )
    (net (code "14") (name "/ADS1P_6") (class "Default")
      (node (ref "C152") (pin "2") (pinfunction "2_2") (pintype "passive"))
      (node (ref "P_ADS_P") (pin "6") (pinfunction "6_6") (pintype "passive"))
      (node (ref "R89") (pin "1") (pinfunction "1_1") (pintype "passive"))
    )
    (net (code "15") (name "/ADS1P_7") (class "Default")
      (node (ref "C150") (pin "2") (pinfunction "2_2") (pintype "passive"))
      (node (ref "P_ADS_P") (pin "7") (pinfunction "7_7") (pintype "passive"))
      (node (ref "R87") (pin "1") (pinfunction "1_1") (pintype "passive"))
    )
    (net (code "16") (name "/ADS1P_8") (class "Default")
      (node (ref "C148") (pin "2") (pinfunction "2_2") (pintype "passive"))
      (node (ref "P_ADS_P") (pin "8") (pinfunction "8_8") (pintype "passive"))
      (node (ref "R85") (pin "1") (pinfunction "1_1") (pintype "passive"))
    )
    (net (code "17") (name "/ADS1_NA") (class "Default")
      (node (ref "P_ADS1_NA") (pin "2") (pinfunction "2_2") (pintype "passive"))
      (node (ref "P_ADS_NA") (pin "2") (pinfunction "2_2") (pintype "passive"))
      (node (ref "P_ADS_SHARE") (pin "5") (pinfunction "5_5") (pintype "passive"))
    )
    (net (code "18") (name "/ADS1_SRB1") (class "Default")
      (node (ref "C121") (pin "2") (pinfunction "2_2") (pintype "passive"))
      (node (ref "P_ADS_SRB") (pin "1") (pinfunction "1_1") (pintype "passive"))
      (node (ref "R60") (pin "2") (pinfunction "2_2") (pintype "passive"))
      (node (ref "U_ADS_1") (pin "17") (pinfunction "SRB1_17") (pintype "passive"))
    )
    (net (code "19") (name "/ADS1_SRB1_IN") (class "Default")
      (node (ref "P_ADS1_SRB1_IN") (pin "1") (pinfunction "1_1") (pintype "passive"))
      (node (ref "P_ADS_SHARE") (pin "1") (pinfunction "1_1") (pintype "passive"))
      (node (ref "P_ADS_SRB1") (pin "2") (pinfunction "2_2") (pintype "passive"))
      (node (ref "U_OPA_6") (pin "3") (pintype "passive"))
    )
    (net (code "20") (name "/ADS1_SRB2") (class "Default")
      (node (ref "C122") (pin "1") (pinfunction "1_1") (pintype "passive"))
      (node (ref "P_ADS_SRB") (pin "3") (pinfunction "3_3") (pintype "passive"))
      (node (ref "R61") (pin "2") (pinfunction "2_2") (pintype "passive"))
      (node (ref "U_ADS_1") (pin "18") (pinfunction "SRB2_18") (pintype "passive"))
    )
    (net (code "21") (name "/ADS1_SRB2_IN") (class "Default")
      (node (ref "P_ADS1_SRB2_IN") (pin "2") (pinfunction "2_2") (pintype "passive"))
      (node (ref "P_ADS2_SRB2_IN") (pin "2") (pinfunction "2_2") (pintype "passive"))
      (node (ref "P_ADS_SHARE") (pin "2") (pinfunction "2_2") (pintype "passive"))
      (node (ref "P_ADS_SHARE") (pin "4") (pinfunction "4_4") (pintype "passive"))
      (node (ref "P_ADS_SRB2") (pin "1") (pinfunction "1_1") (pintype "passive"))
      (node (ref "U_OPA_5") (pin "3") (pintype "passive"))
      (node (ref "U_OPA_7") (pin "3") (pintype "passive"))
    )
    (net (code "22") (name "/ADS2N_1") (class "Default")
      (node (ref "C145") (pin "2") (pinfunction "2_2") (pintype "passive"))
      (node (ref "P_ADS2_NA") (pin "1") (pinfunction "1_1") (pintype "passive"))
      (node (ref "P_ADS2_NA_1") (pin "1") (pinfunction "1_1") (pintype "passive"))
      (node (ref "P_ADS2_NA_2") (pin "1") (pinfunction "1_1") (pintype "passive"))
      (node (ref "P_ADS2_NA_2") (pin "2") (pinfunction "2_2") (pintype "passive"))
      (node (ref "R82") (pin "1") (pinfunction "1_1") (pintype "passive"))
    )
    (net (code "23") (name "/ADS2N_2") (class "Default")
      (node (ref "C143") (pin "2") (pinfunction "2_2") (pintype "passive"))
      (node (ref "P_ADS2_NA_1") (pin "2") (pinfunction "2_2") (pintype "passive"))
      (node (ref "P_ADS2_NA_2") (pin "3") (pinfunction "3_3") (pintype "passive"))
      (node (ref "P_ADS2_NA_2") (pin "4") (pinfunction "4_4") (pintype "passive"))
      (node (ref "R80") (pin "1") (pinfunction "1_1") (pintype "passive"))
    )
    (net (code "24") (name "/ADS2N_3") (class "Default")
      (node (ref "C141") (pin "2") (pinfunction "2_2") (pintype "passive"))
      (node (ref "P_ADS2_NA_1") (pin "3") (pinfunction "3_3") (pintype "passive"))
      (node (ref "P_ADS2_NA_2") (pin "5") (pinfunction "5_5") (pintype "passive"))
      (node (ref "P_ADS2_NA_2") (pin "6") (pinfunction "6_6") (pintype "passive"))
      (node (ref "R78") (pin "1") (pinfunction "1_1") (pintype "passive"))
    )
    (net (code "25") (name "/ADS2N_4") (class "Default")
      (node (ref "C139") (pin "2") (pinfunction "2_2") (pintype "passive"))
      (node (ref "P_ADS2_NA_1") (pin "4") (pinfunction "4_4") (pintype "passive"))
      (node (ref "P_ADS2_NA_2") (pin "7") (pinfunction "7_7") (pintype "passive"))
      (node (ref "P_ADS2_NA_2") (pin "8") (pinfunction "8_8") (pintype "passive"))
      (node (ref "R76") (pin "1") (pinfunction "1_1") (pintype "passive"))
    )
    (net (code "26") (name "/ADS2N_5") (class "Default")
      (node (ref "C137") (pin "2") (pinfunction "2_2") (pintype "passive"))
      (node (ref "P_ADS2_NA_1") (pin "5") (pinfunction "5_5") (pintype "passive"))
      (node (ref "P_ADS2_NA_2") (pin "10") (pinfunction "10_10") (pintype "passive"))
      (node (ref "P_ADS2_NA_2") (pin "9") (pinfunction "9_9") (pintype "passive"))
      (node (ref "R74") (pin "1") (pinfunction "1_1") (pintype "passive"))
    )
    (net (code "27") (name "/ADS2N_6") (class "Default")
      (node (ref "C135") (pin "2") (pinfunction "2_2") (pintype "passive"))
      (node (ref "P_ADS2_NA_1") (pin "6") (pinfunction "6_6") (pintype "passive"))
      (node (ref "P_ADS2_NA_2") (pin "11") (pinfunction "11_11") (pintype "passive"))
      (node (ref "P_ADS2_NA_2") (pin "12") (pinfunction "12_12") (pintype "passive"))
      (node (ref "R72") (pin "1") (pinfunction "1_1") (pintype "passive"))
    )
    (net (code "28") (name "/ADS2N_7") (class "Default")
      (node (ref "C133") (pin "2") (pinfunction "2_2") (pintype "passive"))
      (node (ref "P_ADS2_NA_1") (pin "7") (pinfunction "7_7") (pintype "passive"))
      (node (ref "P_ADS2_NA_2") (pin "13") (pinfunction "13_13") (pintype "passive"))
      (node (ref "P_ADS2_NA_2") (pin "14") (pinfunction "14_14") (pintype "passive"))
      (node (ref "R70") (pin "1") (pinfunction "1_1") (pintype "passive"))
    )
    (net (code "29") (name "/ADS2N_8") (class "Default")
      (node (ref "C131") (pin "2") (pinfunction "2_2") (pintype "passive"))
      (node (ref "P_ADS2_NA_1") (pin "8") (pinfunction "8_8") (pintype "passive"))
      (node (ref "P_ADS2_NA_2") (pin "15") (pinfunction "15_15") (pintype "passive"))
      (node (ref "P_ADS2_NA_2") (pin "16") (pinfunction "16_16") (pintype "passive"))
      (node (ref "R68") (pin "1") (pinfunction "1_1") (pintype "passive"))
    )
    (net (code "30") (name "/ADS2P_1") (class "Default")
      (node (ref "C146") (pin "2") (pinfunction "2_2") (pintype "passive"))
      (node (ref "P_ADS_P") (pin "9") (pinfunction "9_9") (pintype "passive"))
      (node (ref "R83") (pin "1") (pinfunction "1_1") (pintype "passive"))
    )
    (net (code "31") (name "/ADS2P_2") (class "Default")
      (node (ref "C144") (pin "2") (pinfunction "2_2") (pintype "passive"))
      (node (ref "P_ADS_P") (pin "10") (pinfunction "10_10") (pintype "passive"))
      (node (ref "R81") (pin "1") (pinfunction "1_1") (pintype "passive"))
    )
    (net (code "32") (name "/ADS2P_3") (class "Default")
      (node (ref "C142") (pin "2") (pinfunction "2_2") (pintype "passive"))
      (node (ref "P_ADS_P") (pin "11") (pinfunction "11_11") (pintype "passive"))
      (node (ref "R79") (pin "1") (pinfunction "1_1") (pintype "passive"))
    )
    (net (code "33") (name "/ADS2P_4") (class "Default")
      (node (ref "C140") (pin "2") (pinfunction "2_2") (pintype "passive"))
      (node (ref "P_ADS_P") (pin "12") (pinfunction "12_12") (pintype "passive"))
      (node (ref "R77") (pin "1") (pinfunction "1_1") (pintype "passive"))
    )
    (net (code "34") (name "/ADS2P_5") (class "Default")
      (node (ref "C138") (pin "2") (pinfunction "2_2") (pintype "passive"))
      (node (ref "P_ADS_P") (pin "13") (pinfunction "13_13") (pintype "passive"))
      (node (ref "R75") (pin "1") (pinfunction "1_1") (pintype "passive"))
    )
    (net (code "35") (name "/ADS2P_6") (class "Default")
      (node (ref "C136") (pin "2") (pinfunction "2_2") (pintype "passive"))
      (node (ref "P_ADS_P") (pin "14") (pinfunction "14_14") (pintype "passive"))
      (node (ref "R73") (pin "1") (pinfunction "1_1") (pintype "passive"))
    )
    (net (code "36") (name "/ADS2P_7") (class "Default")
      (node (ref "C134") (pin "2") (pinfunction "2_2") (pintype "passive"))
      (node (ref "P_ADS_P") (pin "15") (pinfunction "15_15") (pintype "passive"))
      (node (ref "R71") (pin "1") (pinfunction "1_1") (pintype "passive"))
    )
    (net (code "37") (name "/ADS2P_8") (class "Default")
      (node (ref "C132") (pin "2") (pinfunction "2_2") (pintype "passive"))
      (node (ref "P_ADS_P") (pin "16") (pinfunction "16_16") (pintype "passive"))
      (node (ref "R69") (pin "1") (pinfunction "1_1") (pintype "passive"))
    )
    (net (code "38") (name "/ADS2_NA") (class "Default")
      (node (ref "P_ADS2_NA") (pin "2") (pinfunction "2_2") (pintype "passive"))
      (node (ref "P_ADS_NA") (pin "1") (pinfunction "1_1") (pintype "passive"))
      (node (ref "P_ADS_SHARE") (pin "6") (pinfunction "6_6") (pintype "passive"))
    )
    (net (code "39") (name "/ADS2_OUT") (class "Default")
      (node (ref "U_ADS_1") (pin "41") (pinfunction "DAISY_IN_41") (pintype "passive"))
      (node (ref "U_ADS_2") (pin "43") (pinfunction "DOUT_43") (pintype "passive"))
    )
    (net (code "40") (name "/ADS2_SRB1") (class "Default")
      (node (ref "C106") (pin "2") (pinfunction "2_2") (pintype "passive"))
      (node (ref "P_ADS_SRB") (pin "2") (pinfunction "2_2") (pintype "passive"))
      (node (ref "R51") (pin "2") (pinfunction "2_2") (pintype "passive"))
      (node (ref "U_ADS_2") (pin "17") (pinfunction "SRB1_17") (pintype "passive"))
      (node (ref "U_OPA_4") (pin "2") (pintype "passive"))
      (node (ref "U_OPA_4") (pin "6") (pintype "passive"))
    )
    (net (code "41") (name "/ADS2_SRB1_IN") (class "Default")
      (node (ref "P_ADS2_SRB1_IN") (pin "1") (pinfunction "1_1") (pintype "passive"))
      (node (ref "P_ADS_SHARE") (pin "3") (pinfunction "3_3") (pintype "passive"))
      (node (ref "P_ADS_SRB1") (pin "1") (pinfunction "1_1") (pintype "passive"))
      (node (ref "P_ADS_SRB2") (pin "2") (pinfunction "2_2") (pintype "passive"))
      (node (ref "U_OPA_4") (pin "3") (pintype "passive"))
    )
    (net (code "42") (name "/ADS2_SRB2") (class "Default")
      (node (ref "C108") (pin "1") (pinfunction "1_1") (pintype "passive"))
      (node (ref "P_ADS_SRB") (pin "4") (pinfunction "4_4") (pintype "passive"))
      (node (ref "R52") (pin "2") (pinfunction "2_2") (pintype "passive"))
      (node (ref "U_ADS_2") (pin "18") (pinfunction "SRB2_18") (pintype "passive"))
      (node (ref "U_OPA_5") (pin "2") (pintype "passive"))
      (node (ref "U_OPA_5") (pin "6") (pintype "passive"))
    )
    (net (code "43") (name "/ADS_CLK") (class "Default")
      (node (ref "R58") (pin "1") (pinfunction "1_1") (pintype "passive"))
      (node (ref "R67") (pin "1") (pinfunction "1_1") (pintype "passive"))
      (node (ref "U_ADS_1") (pin "37") (pinfunction "CLK_37") (pintype "passive"))
      (node (ref "U_ADS_2") (pin "37") (pinfunction "CLK_37") (pintype "passive"))
      (node (ref "U_ADS_3") (pin "3") (pinfunction "OUT_3") (pintype "passive"))
    )
    (net (code "44") (name "/ADS_CS") (class "Default")
      (node (ref "P_ADS") (pin "13") (pinfunction "13_13") (pintype "passive"))
      (node (ref "U_ADS_1") (pin "39") (pinfunction "~{C}S_39") (pintype "passive"))
      (node (ref "U_ADS_2") (pin "39") (pinfunction "~{C}S_39") (pintype "passive"))
    )
    (net (code "45") (name "/ADS_DRDY") (class "Default")
      (node (ref "P_ADS") (pin "9") (pinfunction "9_9") (pintype "passive"))
      (node (ref "U_ADS_1") (pin "47") (pinfunction "~{DRD}Y_47") (pintype "passive"))
    )
    (net (code "46") (name "/ADS_GPIO") (class "Default")
      (node (ref "D6") (pin "2") (pinfunction "K_2") (pintype "passive"))
      (node (ref "U_ADS_1") (pin "42") (pinfunction "GPIO1_42") (pintype "passive"))
    )
    (net (code "47") (name "/ADS_PWDN") (class "Default")
      (node (ref "P_ADS") (pin "3") (pinfunction "3_3") (pintype "passive"))
      (node (ref "U_ADS_1") (pin "35") (pinfunction "~{PWD}N_35") (pintype "passive"))
      (node (ref "U_ADS_2") (pin "35") (pinfunction "~{PWD}N_35") (pintype "passive"))
    )
    (net (code "48") (name "/ADS_REF") (class "Default")
      (node (ref "U_OPA_3") (pin "2") (pintype "passive"))
      (node (ref "U_OPA_3") (pin "6") (pintype "passive"))
    )
    (net (code "49") (name "/ADS_RESET") (class "Default")
      (node (ref "P_ADS") (pin "5") (pinfunction "5_5") (pintype "passive"))
      (node (ref "U_ADS_1") (pin "36") (pinfunction "~{RESE}T_36") (pintype "passive"))
      (node (ref "U_ADS_2") (pin "36") (pinfunction "~{RESE}T_36") (pintype "passive"))
    )
    (net (code "50") (name "/ADS_START") (class "Default")
      (node (ref "P_ADS") (pin "7") (pinfunction "7_7") (pintype "passive"))
      (node (ref "U_ADS_1") (pin "38") (pinfunction "START_38") (pintype "passive"))
      (node (ref "U_ADS_2") (pin "38") (pinfunction "START_38") (pintype "passive"))
    )
    (net (code "51") (name "/BIAS_DRV") (class "Default")
      (node (ref "C109") (pin "2") (pinfunction "2_2") (pintype "passive"))
      (node (ref "C123") (pin "2") (pinfunction "2_2") (pintype "passive"))
      (node (ref "P_ADS1_BIAS") (pin "2") (pinfunction "2_2") (pintype "passive"))
      (node (ref "P_ADS2_BIAS") (pin "2") (pinfunction "2_2") (pintype "passive"))
      (node (ref "P_ADS_SHARE") (pin "8") (pinfunction "8_8") (pintype "passive"))
      (node (ref "R53") (pin "2") (pinfunction "2_2") (pintype "passive"))
      (node (ref "R54") (pin "1") (pinfunction "1_1") (pintype "passive"))
      (node (ref "R62") (pin "2") (pinfunction "2_2") (pintype "passive"))
      (node (ref "R63") (pin "1") (pinfunction "1_1") (pintype "passive"))
    )
    (net (code "52") (name "/BIAS_ELEC") (class "Default")
      (node (ref "P_ADS1_BIAS") (pin "1") (pinfunction "1_1") (pintype "passive"))
      (node (ref "P_ADS2_BIAS") (pin "1") (pinfunction "1_1") (pintype "passive"))
      (node (ref "P_ADS_SHARE") (pin "7") (pinfunction "7_7") (pintype "passive"))
    )
    (net (code "53") (name "/OS_EN") (class "Default")
      (node (ref "P_ADS") (pin "1") (pinfunction "1_1") (pintype "passive"))
      (node (ref "U_ADS_3") (pin "1") (pinfunction "EC_1") (pintype "passive"))
    )
    (net (code "54") (name "/PB7") (class "Default")
      (node (ref "P_ADS") (pin "2") (pinfunction "2_2") (pintype "passive"))
    )
    (net (code "55") (name "/PB8") (class "Default")
      (node (ref "P_ADS") (pin "4") (pinfunction "4_4") (pintype "passive"))
    )
    (net (code "56") (name "/PB9") (class "Default")
      (node (ref "P_ADS") (pin "6") (pinfunction "6_6") (pintype "passive"))
    )
    (net (code "57") (name "/PB10") (class "Default")
      (node (ref "P_ADS") (pin "8") (pinfunction "8_8") (pintype "passive"))
    )
    (net (code "58") (name "/PB11") (class "Default")
      (node (ref "P_ADS") (pin "10") (pinfunction "10_10") (pintype "passive"))
    )
    (net (code "59") (name "/PB12") (class "Default")
      (node (ref "P_ADS") (pin "14") (pinfunction "14_14") (pintype "passive"))
    )
    (net (code "60") (name "/PB13") (class "Default")
      (node (ref "P_ADS") (pin "12") (pinfunction "12_12") (pintype "passive"))
    )
    (net (code "61") (name "/PB14") (class "Default")
      (node (ref "P_ADS") (pin "18") (pinfunction "18_18") (pintype "passive"))
    )
    (net (code "62") (name "/PB15") (class "Default")
      (node (ref "P_ADS") (pin "16") (pinfunction "16_16") (pintype "passive"))
    )
    (net (code "63") (name "/SPI_CLK") (class "Default")
      (node (ref "P_ADS") (pin "11") (pinfunction "11_11") (pintype "passive"))
      (node (ref "U_ADS_1") (pin "40") (pinfunction "SCLK_40") (pintype "passive"))
      (node (ref "U_ADS_2") (pin "40") (pinfunction "SCLK_40") (pintype "passive"))
    )
    (net (code "64") (name "/SPI_DIN") (class "Default")
      (node (ref "P_ADS") (pin "15") (pinfunction "15_15") (pintype "passive"))
      (node (ref "U_ADS_1") (pin "34") (pinfunction "DIN_34") (pintype "passive"))
      (node (ref "U_ADS_2") (pin "34") (pinfunction "DIN_34") (pintype "passive"))
    )
    (net (code "65") (name "/SPI_DOUT") (class "Default")
      (node (ref "P_ADS") (pin "17") (pinfunction "17_17") (pintype "passive"))
      (node (ref "U_ADS_1") (pin "43") (pinfunction "DOUT_43") (pintype "passive"))
    )
    (net (code "66") (name "AGND") (class "Default")
      (node (ref "C103") (pin "2") (pinfunction "2_2") (pintype "passive"))
      (node (ref "C104") (pin "2") (pinfunction "2_2") (pintype "passive"))
      (node (ref "C105") (pin "2") (pinfunction "2_2") (pintype "passive"))
      (node (ref "C106") (pin "1") (pinfunction "1_1") (pintype "passive"))
      (node (ref "C107") (pin "2") (pinfunction "2_2") (pintype "passive"))
      (node (ref "C108") (pin "2") (pinfunction "2_2") (pintype "passive"))
      (node (ref "C110") (pin "2") (pinfunction "2_2") (pintype "passive"))
      (node (ref "C111") (pin "2") (pinfunction "2_2") (pintype "passive"))
      (node (ref "C117") (pin "2") (pinfunction "2_2") (pintype "passive"))
      (node (ref "C118") (pin "2") (pinfunction "2_2") (pintype "passive"))
      (node (ref "C119") (pin "2") (pinfunction "2_2") (pintype "passive"))
      (node (ref "C120") (pin "2") (pinfunction "2_2") (pintype "passive"))
      (node (ref "C121") (pin "1") (pinfunction "1_1") (pintype "passive"))
      (node (ref "C122") (pin "2") (pinfunction "2_2") (pintype "passive"))
      (node (ref "C124") (pin "2") (pinfunction "2_2") (pintype "passive"))
      (node (ref "C125") (pin "2") (pinfunction "2_2") (pintype "passive"))
      (node (ref "C131") (pin "1") (pinfunction "1_1") (pintype "passive"))
      (node (ref "C132") (pin "1") (pinfunction "1_1") (pintype "passive"))
      (node (ref "C133") (pin "1") (pinfunction "1_1") (pintype "passive"))
      (node (ref "C134") (pin "1") (pinfunction "1_1") (pintype "passive"))
      (node (ref "C135") (pin "1") (pinfunction "1_1") (pintype "passive"))
      (node (ref "C136") (pin "1") (pinfunction "1_1") (pintype "passive"))
      (node (ref "C137") (pin "1") (pinfunction "1_1") (pintype "passive"))
      (node (ref "C138") (pin "1") (pinfunction "1_1") (pintype "passive"))
      (node (ref "C139") (pin "1") (pinfunction "1_1") (pintype "passive"))
      (node (ref "C140") (pin "1") (pinfunction "1_1") (pintype "passive"))
      (node (ref "C141") (pin "1") (pinfunction "1_1") (pintype "passive"))
      (node (ref "C142") (pin "1") (pinfunction "1_1") (pintype "passive"))
      (node (ref "C143") (pin "1") (pinfunction "1_1") (pintype "passive"))
      (node (ref "C144") (pin "1") (pinfunction "1_1") (pintype "passive"))
      (node (ref "C145") (pin "1") (pinfunction "1_1") (pintype "passive"))
      (node (ref "C146") (pin "1") (pinfunction "1_1") (pintype "passive"))
      (node (ref "C147") (pin "1") (pinfunction "1_1") (pintype "passive"))
      (node (ref "C148") (pin "1") (pinfunction "1_1") (pintype "passive"))
      (node (ref "C149") (pin "1") (pinfunction "1_1") (pintype "passive"))
      (node (ref "C150") (pin "1") (pinfunction "1_1") (pintype "passive"))
      (node (ref "C151") (pin "1") (pinfunction "1_1") (pintype "passive"))
      (node (ref "C152") (pin "1") (pinfunction "1_1") (pintype "passive"))
      (node (ref "C153") (pin "1") (pinfunction "1_1") (pintype "passive"))
      (node (ref "C154") (pin "1") (pinfunction "1_1") (pintype "passive"))
      (node (ref "C155") (pin "1") (pinfunction "1_1") (pintype "passive"))
      (node (ref "C156") (pin "1") (pinfunction "1_1") (pintype "passive"))
      (node (ref "C157") (pin "1") (pinfunction "1_1") (pintype "passive"))
      (node (ref "C158") (pin "1") (pinfunction "1_1") (pintype "passive"))
      (node (ref "C159") (pin "1") (pinfunction "1_1") (pintype "passive"))
      (node (ref "C160") (pin "1") (pinfunction "1_1") (pintype "passive"))
      (node (ref "C161") (pin "1") (pinfunction "1_1") (pintype "passive"))
      (node (ref "C162") (pin "1") (pinfunction "1_1") (pintype "passive"))
      (node (ref "C163") (pin "2") (pinfunction "2_2") (pintype "passive"))
      (node (ref "C164") (pin "2") (pinfunction "2_2") (pintype "passive"))
      (node (ref "U_ADS_1") (pin "31") (pinfunction "RESV1_31") (pintype "passive"))
      (node (ref "U_ADS_2") (pin "31") (pinfunction "RESV1_31") (pintype "passive"))
    )
    (net (code "67") (name "AVDD") (class "Default")
      (node (ref "C103") (pin "1") (pinfunction "1_1") (pintype "passive"))
      (node (ref "C105") (pin "1") (pinfunction "1_1") (pintype "passive"))
      (node (ref "C117") (pin "1") (pinfunction "1_1") (pintype "passive"))
      (node (ref "C119") (pin "1") (pinfunction "1_1") (pintype "passive"))
      (node (ref "C163") (pin "1") (pinfunction "1_1") (pintype "passive"))
      (node (ref "R100") (pin "1") (pinfunction "1_1") (pintype "passive"))
      (node (ref "U_ADS_1") (pin "19") (pinfunction "AVDD_19") (pintype "passive"))
      (node (ref "U_ADS_1") (pin "21") (pinfunction "AVDD_21") (pintype "passive"))
      (node (ref "U_ADS_1") (pin "22") (pinfunction "AVDD_22") (pintype "passive"))
      (node (ref "U_ADS_1") (pin "54") (pinfunction "AVDD1_54") (pintype "passive"))
      (node (ref "U_ADS_1") (pin "56") (pinfunction "AVDD_56") (pintype "passive"))
      (node (ref "U_ADS_1") (pin "59") (pinfunction "AVDD_59") (pintype "passive"))
      (node (ref "U_ADS_2") (pin "19") (pinfunction "AVDD_19") (pintype "passive"))
      (node (ref "U_ADS_2") (pin "21") (pinfunction "AVDD_21") (pintype "passive"))
      (node (ref "U_ADS_2") (pin "22") (pinfunction "AVDD_22") (pintype "passive"))
      (node (ref "U_ADS_2") (pin "54") (pinfunction "AVDD1_54") (pintype "passive"))
      (node (ref "U_ADS_2") (pin "56") (pinfunction "AVDD_56") (pintype "passive"))
      (node (ref "U_ADS_2") (pin "59") (pinfunction "AVDD_59") (pintype "passive"))
      (node (ref "U_OPA_3") (pin "7") (pintype "passive"))
      (node (ref "U_OPA_4") (pin "7") (pintype "passive"))
      (node (ref "U_OPA_5") (pin "7") (pintype "passive"))
      (node (ref "U_OPA_6") (pin "7") (pintype "passive"))
      (node (ref "U_OPA_7") (pin "7") (pintype "passive"))
    )
    (net (code "68") (name "AVSS") (class "Default")
      (node (ref "C104") (pin "1") (pinfunction "1_1") (pintype "passive"))
      (node (ref "C107") (pin "1") (pinfunction "1_1") (pintype "passive"))
      (node (ref "C110") (pin "1") (pinfunction "1_1") (pintype "passive"))
      (node (ref "C111") (pin "1") (pinfunction "1_1") (pintype "passive"))
      (node (ref "C112") (pin "1") (pinfunction "1_1") (pintype "passive"))
      (node (ref "C113") (pin "2") (pinfunction "2_2") (pintype "passive"))
      (node (ref "C114") (pin "2") (pinfunction "2_2") (pintype "passive"))
      (node (ref "C115") (pin "1") (pinfunction "1_1") (pintype "passive"))
      (node (ref "C116") (pin "1") (pinfunction "1_1") (pintype "passive"))
      (node (ref "C118") (pin "1") (pinfunction "1_1") (pintype "passive"))
      (node (ref "C120") (pin "1") (pinfunction "1_1") (pintype "passive"))
      (node (ref "C124") (pin "1") (pinfunction "1_1") (pintype "passive"))
      (node (ref "C125") (pin "1") (pinfunction "1_1") (pintype "passive"))
      (node (ref "C126") (pin "1") (pinfunction "1_1") (pintype "passive"))
      (node (ref "C127") (pin "2") (pinfunction "2_2") (pintype "passive"))
      (node (ref "C128") (pin "2") (pinfunction "2_2") (pintype "passive"))
      (node (ref "C129") (pin "1") (pinfunction "1_1") (pintype "passive"))
      (node (ref "C130") (pin "1") (pinfunction "1_1") (pintype "passive"))
      (node (ref "C164") (pin "1") (pinfunction "1_1") (pintype "passive"))
      (node (ref "C165") (pin "2") (pinfunction "2_2") (pintype "passive"))
      (node (ref "C166") (pin "2") (pinfunction "2_2") (pintype "passive"))
      (node (ref "C167") (pin "2") (pinfunction "2_2") (pintype "passive"))
      (node (ref "C168") (pin "2") (pinfunction "2_2") (pintype "passive"))
      (node (ref "R101") (pin "2") (pinfunction "2_2") (pintype "passive"))
      (node (ref "U_ADS_1") (pin "20") (pinfunction "AVSS_20") (pintype "passive"))
      (node (ref "U_ADS_1") (pin "23") (pinfunction "AVSS_23") (pintype "passive"))
      (node (ref "U_ADS_1") (pin "25") (pinfunction "VREFN_25") (pintype "passive"))
      (node (ref "U_ADS_1") (pin "32") (pinfunction "AVSS_32") (pintype "passive"))
      (node (ref "U_ADS_1") (pin "53") (pinfunction "AVSS1_53") (pintype "passive"))
      (node (ref "U_ADS_1") (pin "57") (pinfunction "AVSS_57") (pintype "passive"))
      (node (ref "U_ADS_1") (pin "58") (pinfunction "AVSS_58") (pintype "passive"))
      (node (ref "U_ADS_2") (pin "20") (pinfunction "AVSS_20") (pintype "passive"))
      (node (ref "U_ADS_2") (pin "23") (pinfunction "AVSS_23") (pintype "passive"))
      (node (ref "U_ADS_2") (pin "25") (pinfunction "VREFN_25") (pintype "passive"))
      (node (ref "U_ADS_2") (pin "32") (pinfunction "AVSS_32") (pintype "passive"))
      (node (ref "U_ADS_2") (pin "53") (pinfunction "AVSS1_53") (pintype "passive"))
      (node (ref "U_ADS_2") (pin "57") (pinfunction "AVSS_57") (pintype "passive"))
      (node (ref "U_ADS_2") (pin "58") (pinfunction "AVSS_58") (pintype "passive"))
      (node (ref "U_OPA_3") (pin "4") (pintype "passive"))
      (node (ref "U_OPA_4") (pin "4") (pintype "passive"))
      (node (ref "U_OPA_5") (pin "4") (pintype "passive"))
      (node (ref "U_OPA_6") (pin "4") (pintype "passive"))
      (node (ref "U_OPA_7") (pin "4") (pintype "passive"))
    )
    (net (code "69") (name "DGND") (class "Default")
      (node (ref "P_ADS1_CLK") (pin "3") (pinfunction "3_3") (pintype "passive"))
      (node (ref "P_ADS2_CLK") (pin "3") (pinfunction "3_3") (pintype "passive"))
      (node (ref "R55") (pin "2") (pinfunction "2_2") (pintype "passive"))
      (node (ref "R56") (pin "2") (pinfunction "2_2") (pintype "passive"))
      (node (ref "R57") (pin "2") (pinfunction "2_2") (pintype "passive"))
      (node (ref "R59") (pin "1") (pinfunction "1_1") (pintype "passive"))
      (node (ref "R64") (pin "2") (pinfunction "2_2") (pintype "passive"))
      (node (ref "R65") (pin "2") (pinfunction "2_2") (pintype "passive"))
      (node (ref "R66") (pin "2") (pinfunction "2_2") (pintype "passive"))
      (node (ref "U_ADS_1") (pin "33") (pinfunction "DGND_33") (pintype "passive"))
      (node (ref "U_ADS_1") (pin "49") (pinfunction "DGND_49") (pintype "passive"))
      (node (ref "U_ADS_1") (pin "51") (pinfunction "DGND_51") (pintype "passive"))
      (node (ref "U_ADS_2") (pin "33") (pinfunction "DGND_33") (pintype "passive"))
      (node (ref "U_ADS_2") (pin "41") (pinfunction "DAISY_IN_41") (pintype "passive"))
      (node (ref "U_ADS_2") (pin "49") (pinfunction "DGND_49") (pintype "passive"))
      (node (ref "U_ADS_2") (pin "51") (pinfunction "DGND_51") (pintype "passive"))
      (node (ref "U_ADS_3") (pin "2") (pinfunction "GND_2") (pintype "passive"))
    )
    (net (code "70") (name "Net-(D6-A)") (class "Default")
      (node (ref "D6") (pin "1") (pinfunction "A_1") (pintype "passive"))
      (node (ref "R102") (pin "2") (pinfunction "2_2") (pintype "passive"))
    )
    (net (code "71") (name "Net-(P_ADS1_SRB1_IN-Pad2)") (class "Default")
      (node (ref "P_ADS1_SRB1_IN") (pin "2") (pinfunction "2_2") (pintype "passive"))
      (node (ref "R60") (pin "1") (pinfunction "1_1") (pintype "passive"))
      (node (ref "U_OPA_6") (pin "2") (pintype "passive"))
      (node (ref "U_OPA_6") (pin "6") (pintype "passive"))
    )
    (net (code "72") (name "Net-(P_ADS1_SRB2_IN-Pad1)") (class "Default")
      (node (ref "P_ADS1_SRB2_IN") (pin "1") (pinfunction "1_1") (pintype "passive"))
      (node (ref "R61") (pin "1") (pinfunction "1_1") (pintype "passive"))
      (node (ref "U_OPA_7") (pin "2") (pintype "passive"))
      (node (ref "U_OPA_7") (pin "6") (pintype "passive"))
    )
    (net (code "73") (name "Net-(P_ADS2_SRB1_IN-Pad2)") (class "Default")
      (node (ref "P_ADS2_SRB1_IN") (pin "2") (pinfunction "2_2") (pintype "passive"))
      (node (ref "R51") (pin "1") (pinfunction "1_1") (pintype "passive"))
    )
    (net (code "74") (name "Net-(P_ADS2_SRB2_IN-Pad1)") (class "Default")
      (node (ref "P_ADS2_SRB2_IN") (pin "1") (pinfunction "1_1") (pintype "passive"))
      (node (ref "R52") (pin "1") (pinfunction "1_1") (pintype "passive"))
    )
    (net (code "75") (name "Net-(R100-Pad2)") (class "Default")
      (node (ref "R100") (pin "2") (pinfunction "2_2") (pintype "passive"))
      (node (ref "R101") (pin "1") (pinfunction "1_1") (pintype "passive"))
      (node (ref "U_OPA_3") (pin "3") (pintype "passive"))
    )
    (net (code "76") (name "Net-(U_ADS_1-BIASIN)") (class "Default")
      (node (ref "P_ADS1_BIAS") (pin "3") (pinfunction "3_3") (pintype "passive"))
      (node (ref "U_ADS_1") (pin "62") (pinfunction "BIASIN_62") (pintype "passive"))
    )
    (net (code "77") (name "Net-(U_ADS_1-BIASINV)") (class "Default")
      (node (ref "C123") (pin "1") (pinfunction "1_1") (pintype "passive"))
      (node (ref "R62") (pin "1") (pinfunction "1_1") (pintype "passive"))
      (node (ref "U_ADS_1") (pin "61") (pinfunction "BIASINV_61") (pintype "passive"))
    )
    (net (code "78") (name "Net-(U_ADS_1-BIASOUT)") (class "Default")
      (node (ref "R63") (pin "2") (pinfunction "2_2") (pintype "passive"))
      (node (ref "U_ADS_1") (pin "63") (pinfunction "BIASOUT_63") (pintype "passive"))
    )
    (net (code "79") (name "Net-(U_ADS_1-CLKSEL)") (class "Default")
      (node (ref "P_ADS2_CLK") (pin "2") (pinfunction "2_2") (pintype "passive"))
      (node (ref "U_ADS_1") (pin "52") (pinfunction "CLKSEL_52") (pintype "passive"))
    )
    (net (code "80") (name "Net-(U_ADS_1-GPIO2)") (class "Default")
      (node (ref "R65") (pin "1") (pinfunction "1_1") (pintype "passive"))
      (node (ref "U_ADS_1") (pin "44") (pinfunction "GPIO2_44") (pintype "passive"))
    )
    (net (code "81") (name "Net-(U_ADS_1-GPIO3)") (class "Default")
      (node (ref "R66") (pin "1") (pinfunction "1_1") (pintype "passive"))
      (node (ref "U_ADS_1") (pin "45") (pinfunction "GPIO3_45") (pintype "passive"))
    )
    (net (code "82") (name "Net-(U_ADS_1-GPIO4)") (class "Default")
      (node (ref "R64") (pin "1") (pinfunction "1_1") (pintype "passive"))
      (node (ref "U_ADS_1") (pin "46") (pinfunction "GPIO4_46") (pintype "passive"))
    )
    (net (code "83") (name "Net-(U_ADS_1-IN1N)") (class "Default")
      (node (ref "R98") (pin "2") (pinfunction "2_2") (pintype "passive"))
      (node (ref "U_ADS_1") (pin "15") (pinfunction "IN1N_15") (pintype "passive"))
    )
    (net (code "84") (name "Net-(U_ADS_1-IN1P)") (class "Default")
      (node (ref "R99") (pin "2") (pinfunction "2_2") (pintype "passive"))
      (node (ref "U_ADS_1") (pin "16") (pinfunction "IN1P_16") (pintype "passive"))
    )
    (net (code "85") (name "Net-(U_ADS_1-IN2N)") (class "Default")
      (node (ref "R96") (pin "2") (pinfunction "2_2") (pintype "passive"))
      (node (ref "U_ADS_1") (pin "13") (pinfunction "IN2N_13") (pintype "passive"))
    )
    (net (code "86") (name "Net-(U_ADS_1-IN2P)") (class "Default")
      (node (ref "R97") (pin "2") (pinfunction "2_2") (pintype "passive"))
      (node (ref "U_ADS_1") (pin "14") (pinfunction "IN2P_14") (pintype "passive"))
    )
    (net (code "87") (name "Net-(U_ADS_1-IN3N)") (class "Default")
      (node (ref "R94") (pin "2") (pinfunction "2_2") (pintype "passive"))
      (node (ref "U_ADS_1") (pin "11") (pinfunction "IN3N_11") (pintype "passive"))
    )
    (net (code "88") (name "Net-(U_ADS_1-IN3P)") (class "Default")
      (node (ref "R95") (pin "2") (pinfunction "2_2") (pintype "passive"))
      (node (ref "U_ADS_1") (pin "12") (pinfunction "IN3P_12") (pintype "passive"))
    )
    (net (code "89") (name "Net-(U_ADS_1-IN4N)") (class "Default")
      (node (ref "R92") (pin "2") (pinfunction "2_2") (pintype "passive"))
      (node (ref "U_ADS_1") (pin "9") (pinfunction "IN4N_9") (pintype "passive"))
    )
    (net (code "90") (name "Net-(U_ADS_1-IN4P)") (class "Default")
      (node (ref "R93") (pin "2") (pinfunction "2_2") (pintype "passive"))
      (node (ref "U_ADS_1") (pin "10") (pinfunction "IN4P_10") (pintype "passive"))
    )
    (net (code "91") (name "Net-(U_ADS_1-IN5N)") (class "Default")
      (node (ref "R90") (pin "2") (pinfunction "2_2") (pintype "passive"))
      (node (ref "U_ADS_1") (pin "7") (pinfunction "IN5N_7") (pintype "passive"))
    )
    (net (code "92") (name "Net-(U_ADS_1-IN5P)") (class "Default")
      (node (ref "R91") (pin "2") (pinfunction "2_2") (pintype "passive"))
      (node (ref "U_ADS_1") (pin "8") (pinfunction "IN5P_8") (pintype "passive"))
    )
    (net (code "93") (name "Net-(U_ADS_1-IN6N)") (class "Default")
      (node (ref "R88") (pin "2") (pinfunction "2_2") (pintype "passive"))
      (node (ref "U_ADS_1") (pin "5") (pinfunction "IN6N_5") (pintype "passive"))
    )
    (net (code "94") (name "Net-(U_ADS_1-IN6P)") (class "Default")
      (node (ref "R89") (pin "2") (pinfunction "2_2") (pintype "passive"))
      (node (ref "U_ADS_1") (pin "6") (pinfunction "IN6P_6") (pintype "passive"))
    )
    (net (code "95") (name "Net-(U_ADS_1-IN7N)") (class "Default")
      (node (ref "R86") (pin "2") (pinfunction "2_2") (pintype "passive"))
      (node (ref "U_ADS_1") (pin "3") (pinfunction "IN7N_3") (pintype "passive"))
    )
    (net (code "96") (name "Net-(U_ADS_1-IN7P)") (class "Default")
      (node (ref "R87") (pin "2") (pinfunction "2_2") (pintype "passive"))
      (node (ref "U_ADS_1") (pin "4") (pinfunction "IN7P_4") (pintype "passive"))
    )
    (net (code "97") (name "Net-(U_ADS_1-IN8N)") (class "Default")
      (node (ref "R84") (pin "2") (pinfunction "2_2") (pintype "passive"))
      (node (ref "U_ADS_1") (pin "1") (pinfunction "IN8N_1") (pintype "passive"))
    )
    (net (code "98") (name "Net-(U_ADS_1-IN8P)") (class "Default")
      (node (ref "R85") (pin "2") (pinfunction "2_2") (pintype "passive"))
      (node (ref "U_ADS_1") (pin "2") (pinfunction "IN8P_2") (pintype "passive"))
    )
    (net (code "99") (name "Net-(U_ADS_1-VCAP1)") (class "Default")
      (node (ref "C129") (pin "2") (pinfunction "2_2") (pintype "passive"))
      (node (ref "U_ADS_1") (pin "28") (pinfunction "VCAP1_28") (pintype "passive"))
    )
    (net (code "100") (name "Net-(U_ADS_1-VCAP2)") (class "Default")
      (node (ref "C130") (pin "2") (pinfunction "2_2") (pintype "passive"))
      (node (ref "U_ADS_1") (pin "30") (pinfunction "VCAP2_30") (pintype "passive"))
    )
    (net (code "101") (name "Net-(U_ADS_1-VCAP3)") (class "Default")
      (node (ref "C167") (pin "1") (pinfunction "1_1") (pintype "passive"))
      (node (ref "C168") (pin "1") (pinfunction "1_1") (pintype "passive"))
      (node (ref "U_ADS_1") (pin "55") (pinfunction "VCAP3_55") (pintype "passive"))
    )
    (net (code "102") (name "Net-(U_ADS_1-VCAP4)") (class "Default")
      (node (ref "C126") (pin "2") (pinfunction "2_2") (pintype "passive"))
      (node (ref "U_ADS_1") (pin "26") (pinfunction "VCAP4_26") (pintype "passive"))
    )
    (net (code "103") (name "Net-(U_ADS_1-VREFP)") (class "Default")
      (node (ref "C127") (pin "1") (pinfunction "1_1") (pintype "passive"))
      (node (ref "C128") (pin "1") (pinfunction "1_1") (pintype "passive"))
      (node (ref "U_ADS_1") (pin "24") (pinfunction "VREFP_24") (pintype "passive"))
    )
    (net (code "104") (name "Net-(U_ADS_2-BIASIN)") (class "Default")
      (node (ref "P_ADS2_BIAS") (pin "3") (pinfunction "3_3") (pintype "passive"))
      (node (ref "U_ADS_2") (pin "62") (pinfunction "BIASIN_62") (pintype "passive"))
    )
    (net (code "105") (name "Net-(U_ADS_2-BIASINV)") (class "Default")
      (node (ref "C109") (pin "1") (pinfunction "1_1") (pintype "passive"))
      (node (ref "R53") (pin "1") (pinfunction "1_1") (pintype "passive"))
      (node (ref "U_ADS_2") (pin "61") (pinfunction "BIASINV_61") (pintype "passive"))
    )
    (net (code "106") (name "Net-(U_ADS_2-BIASOUT)") (class "Default")
      (node (ref "R54") (pin "2") (pinfunction "2_2") (pintype "passive"))
      (node (ref "U_ADS_2") (pin "63") (pinfunction "BIASOUT_63") (pintype "passive"))
    )
    (net (code "107") (name "Net-(U_ADS_2-CLKSEL)") (class "Default")
      (node (ref "P_ADS1_CLK") (pin "2") (pinfunction "2_2") (pintype "passive"))
      (node (ref "U_ADS_2") (pin "52") (pinfunction "CLKSEL_52") (pintype "passive"))
    )
    (net (code "108") (name "Net-(U_ADS_2-GPIO1)") (class "Default")
      (node (ref "R59") (pin "2") (pinfunction "2_2") (pintype "passive"))
      (node (ref "U_ADS_2") (pin "42") (pinfunction "GPIO1_42") (pintype "passive"))
    )
    (net (code "109") (name "Net-(U_ADS_2-GPIO2)") (class "Default")
      (node (ref "R56") (pin "1") (pinfunction "1_1") (pintype "passive"))
      (node (ref "U_ADS_2") (pin "44") (pinfunction "GPIO2_44") (pintype "passive"))
    )
    (net (code "110") (name "Net-(U_ADS_2-GPIO3)") (class "Default")
      (node (ref "R57") (pin "1") (pinfunction "1_1") (pintype "passive"))
      (node (ref "U_ADS_2") (pin "45") (pinfunction "GPIO3_45") (pintype "passive"))
    )
    (net (code "111") (name "Net-(U_ADS_2-GPIO4)") (class "Default")
      (node (ref "R55") (pin "1") (pinfunction "1_1") (pintype "passive"))
      (node (ref "U_ADS_2") (pin "46") (pinfunction "GPIO4_46") (pintype "passive"))
    )
    (net (code "112") (name "Net-(U_ADS_2-IN1N)") (class "Default")
      (node (ref "R82") (pin "2") (pinfunction "2_2") (pintype "passive"))
      (node (ref "U_ADS_2") (pin "15") (pinfunction "IN1N_15") (pintype "passive"))
    )
    (net (code "113") (name "Net-(U_ADS_2-IN1P)") (class "Default")
      (node (ref "R83") (pin "2") (pinfunction "2_2") (pintype "passive"))
      (node (ref "U_ADS_2") (pin "16") (pinfunction "IN1P_16") (pintype "passive"))
    )
    (net (code "114") (name "Net-(U_ADS_2-IN2N)") (class "Default")
      (node (ref "R80") (pin "2") (pinfunction "2_2") (pintype "passive"))
      (node (ref "U_ADS_2") (pin "13") (pinfunction "IN2N_13") (pintype "passive"))
    )
    (net (code "115") (name "Net-(U_ADS_2-IN2P)") (class "Default")
      (node (ref "R81") (pin "2") (pinfunction "2_2") (pintype "passive"))
      (node (ref "U_ADS_2") (pin "14") (pinfunction "IN2P_14") (pintype "passive"))
    )
    (net (code "116") (name "Net-(U_ADS_2-IN3N)") (class "Default")
      (node (ref "R78") (pin "2") (pinfunction "2_2") (pintype "passive"))
      (node (ref "U_ADS_2") (pin "11") (pinfunction "IN3N_11") (pintype "passive"))
    )
    (net (code "117") (name "Net-(U_ADS_2-IN3P)") (class "Default")
      (node (ref "R79") (pin "2") (pinfunction "2_2") (pintype "passive"))
      (node (ref "U_ADS_2") (pin "12") (pinfunction "IN3P_12") (pintype "passive"))
    )
    (net (code "118") (name "Net-(U_ADS_2-IN4N)") (class "Default")
      (node (ref "R76") (pin "2") (pinfunction "2_2") (pintype "passive"))
      (node (ref "U_ADS_2") (pin "9") (pinfunction "IN4N_9") (pintype "passive"))
    )
    (net (code "119") (name "Net-(U_ADS_2-IN4P)") (class "Default")
      (node (ref "R77") (pin "2") (pinfunction "2_2") (pintype "passive"))
      (node (ref "U_ADS_2") (pin "10") (pinfunction "IN4P_10") (pintype "passive"))
    )
    (net (code "120") (name "Net-(U_ADS_2-IN5N)") (class "Default")
      (node (ref "R74") (pin "2") (pinfunction "2_2") (pintype "passive"))
      (node (ref "U_ADS_2") (pin "7") (pinfunction "IN5N_7") (pintype "passive"))
    )
    (net (code "121") (name "Net-(U_ADS_2-IN5P)") (class "Default")
      (node (ref "R75") (pin "2") (pinfunction "2_2") (pintype "passive"))
      (node (ref "U_ADS_2") (pin "8") (pinfunction "IN5P_8") (pintype "passive"))
    )
    (net (code "122") (name "Net-(U_ADS_2-IN6N)") (class "Default")
      (node (ref "R72") (pin "2") (pinfunction "2_2") (pintype "passive"))
      (node (ref "U_ADS_2") (pin "5") (pinfunction "IN6N_5") (pintype "passive"))
    )
    (net (code "123") (name "Net-(U_ADS_2-IN6P)") (class "Default")
      (node (ref "R73") (pin "2") (pinfunction "2_2") (pintype "passive"))
      (node (ref "U_ADS_2") (pin "6") (pinfunction "IN6P_6") (pintype "passive"))
    )
    (net (code "124") (name "Net-(U_ADS_2-IN7N)") (class "Default")
      (node (ref "R70") (pin "2") (pinfunction "2_2") (pintype "passive"))
      (node (ref "U_ADS_2") (pin "3") (pinfunction "IN7N_3") (pintype "passive"))
    )
    (net (code "125") (name "Net-(U_ADS_2-IN7P)") (class "Default")
      (node (ref "R71") (pin "2") (pinfunction "2_2") (pintype "passive"))
      (node (ref "U_ADS_2") (pin "4") (pinfunction "IN7P_4") (pintype "passive"))
    )
    (net (code "126") (name "Net-(U_ADS_2-IN8N)") (class "Default")
      (node (ref "R68") (pin "2") (pinfunction "2_2") (pintype "passive"))
      (node (ref "U_ADS_2") (pin "1") (pinfunction "IN8N_1") (pintype "passive"))
    )
    (net (code "127") (name "Net-(U_ADS_2-IN8P)") (class "Default")
      (node (ref "R69") (pin "2") (pinfunction "2_2") (pintype "passive"))
      (node (ref "U_ADS_2") (pin "2") (pinfunction "IN8P_2") (pintype "passive"))
    )
    (net (code "128") (name "Net-(U_ADS_2-VCAP1)") (class "Default")
      (node (ref "C115") (pin "2") (pinfunction "2_2") (pintype "passive"))
      (node (ref "U_ADS_2") (pin "28") (pinfunction "VCAP1_28") (pintype "passive"))
    )
    (net (code "129") (name "Net-(U_ADS_2-VCAP2)") (class "Default")
      (node (ref "C116") (pin "2") (pinfunction "2_2") (pintype "passive"))
      (node (ref "U_ADS_2") (pin "30") (pinfunction "VCAP2_30") (pintype "passive"))
    )
    (net (code "130") (name "Net-(U_ADS_2-VCAP3)") (class "Default")
      (node (ref "C165") (pin "1") (pinfunction "1_1") (pintype "passive"))
      (node (ref "C166") (pin "1") (pinfunction "1_1") (pintype "passive"))
      (node (ref "U_ADS_2") (pin "55") (pinfunction "VCAP3_55") (pintype "passive"))
    )
    (net (code "131") (name "Net-(U_ADS_2-VCAP4)") (class "Default")
      (node (ref "C112") (pin "2") (pinfunction "2_2") (pintype "passive"))
      (node (ref "U_ADS_2") (pin "26") (pinfunction "VCAP4_26") (pintype "passive"))
    )
    (net (code "132") (name "Net-(U_ADS_2-VREFP)") (class "Default")
      (node (ref "C113") (pin "1") (pinfunction "1_1") (pintype "passive"))
      (node (ref "C114") (pin "1") (pinfunction "1_1") (pintype "passive"))
      (node (ref "U_ADS_2") (pin "24") (pinfunction "VREFP_24") (pintype "passive"))
    )
    (net (code "133") (name "VCC3.3") (class "Default")
      (node (ref "R102") (pin "1") (pinfunction "1_1") (pintype "passive"))
      (node (ref "U_ADS_3") (pin "4") (pinfunction "VDD_4") (pintype "passive"))
    )
    (net (code "134") (name "VCC3.3M") (class "Default")
      (node (ref "P_ADS1_CLK") (pin "1") (pinfunction "1_1") (pintype "passive"))
      (node (ref "P_ADS2_CLK") (pin "1") (pinfunction "1_1") (pintype "passive"))
      (node (ref "R58") (pin "2") (pinfunction "2_2") (pintype "passive"))
      (node (ref "R67") (pin "2") (pinfunction "2_2") (pintype "passive"))
      (node (ref "U_ADS_1") (pin "48") (pinfunction "DVDD_48") (pintype "passive"))
      (node (ref "U_ADS_1") (pin "50") (pinfunction "DVDD_50") (pintype "passive"))
      (node (ref "U_ADS_2") (pin "48") (pinfunction "DVDD_48") (pintype "passive"))
      (node (ref "U_ADS_2") (pin "50") (pinfunction "DVDD_50") (pintype "passive"))
    )
    (net (code "135") (name "unconnected-(U_ADS_1-BIASREF-Pad60)") (class "Default")
      (node (ref "U_ADS_1") (pin "60") (pinfunction "BIASREF_60") (pintype "passive"))
    )
    (net (code "136") (name "unconnected-(U_ADS_1-NC-Pad27)") (class "Default")
      (node (ref "U_ADS_1") (pin "27") (pinfunction "NC_27") (pintype "passive"))
    )
    (net (code "137") (name "unconnected-(U_ADS_1-NC-Pad29)") (class "Default")
      (node (ref "U_ADS_1") (pin "29") (pinfunction "NC_29") (pintype "passive"))
    )
    (net (code "138") (name "unconnected-(U_ADS_1-RESERVED-Pad64)") (class "Default")
      (node (ref "U_ADS_1") (pin "64") (pinfunction "RESERVED_64") (pintype "passive"))
    )
    (net (code "139") (name "unconnected-(U_ADS_2-BIASREF-Pad60)") (class "Default")
      (node (ref "U_ADS_2") (pin "60") (pinfunction "BIASREF_60") (pintype "passive"))
    )
    (net (code "140") (name "unconnected-(U_ADS_2-NC-Pad27)") (class "Default")
      (node (ref "U_ADS_2") (pin "27") (pinfunction "NC_27") (pintype "passive"))
    )
    (net (code "141") (name "unconnected-(U_ADS_2-NC-Pad29)") (class "Default")
      (node (ref "U_ADS_2") (pin "29") (pinfunction "NC_29") (pintype "passive"))
    )
    (net (code "142") (name "unconnected-(U_ADS_2-RESERVED-Pad64)") (class "Default")
      (node (ref "U_ADS_2") (pin "64") (pinfunction "RESERVED_64") (pintype "passive"))
    )
    (net (code "143") (name "unconnected-(U_ADS_2-~{DRD}Y-Pad47)") (class "Default")
      (node (ref "U_ADS_2") (pin "47") (pinfunction "~{DRD}Y_47") (pintype "passive"))
    )
    (net (code "144") (name "unconnected-(U_OPA_3-Pad5)") (class "Default")
      (node (ref "U_OPA_3") (pin "5") (pintype "passive"))
    )
    (net (code "145") (name "unconnected-(U_OPA_3-Pad8)") (class "Default")
      (node (ref "U_OPA_3") (pin "8") (pintype "passive"))
    )
    (net (code "146") (name "unconnected-(U_OPA_4-Pad5)") (class "Default")
      (node (ref "U_OPA_4") (pin "5") (pintype "passive"))
    )
    (net (code "147") (name "unconnected-(U_OPA_4-Pad8)") (class "Default")
      (node (ref "U_OPA_4") (pin "8") (pintype "passive"))
    )
    (net (code "148") (name "unconnected-(U_OPA_5-Pad5)") (class "Default")
      (node (ref "U_OPA_5") (pin "5") (pintype "passive"))
    )
    (net (code "149") (name "unconnected-(U_OPA_5-Pad8)") (class "Default")
      (node (ref "U_OPA_5") (pin "8") (pintype "passive"))
    )
    (net (code "150") (name "unconnected-(U_OPA_6-Pad5)") (class "Default")
      (node (ref "U_OPA_6") (pin "5") (pintype "passive"))
    )
    (net (code "151") (name "unconnected-(U_OPA_6-Pad8)") (class "Default")
      (node (ref "U_OPA_6") (pin "8") (pintype "passive"))
    )
    (net (code "152") (name "unconnected-(U_OPA_7-Pad5)") (class "Default")
      (node (ref "U_OPA_7") (pin "5") (pintype "passive"))
    )
    (net (code "153") (name "unconnected-(U_OPA_7-Pad8)") (class "Default")
      (node (ref "U_OPA_7") (pin "8") (pintype "passive"))
    )
  )
)
